# BasePCB.net
KiCad netlist of a schematic drawn in EAGLE
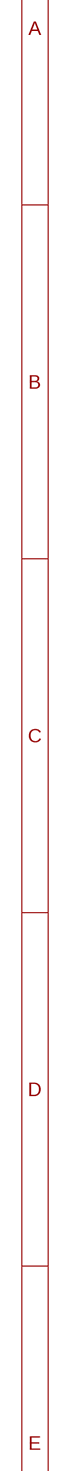
[diagram p0: schematic, sheet 1, part 1 of 2]
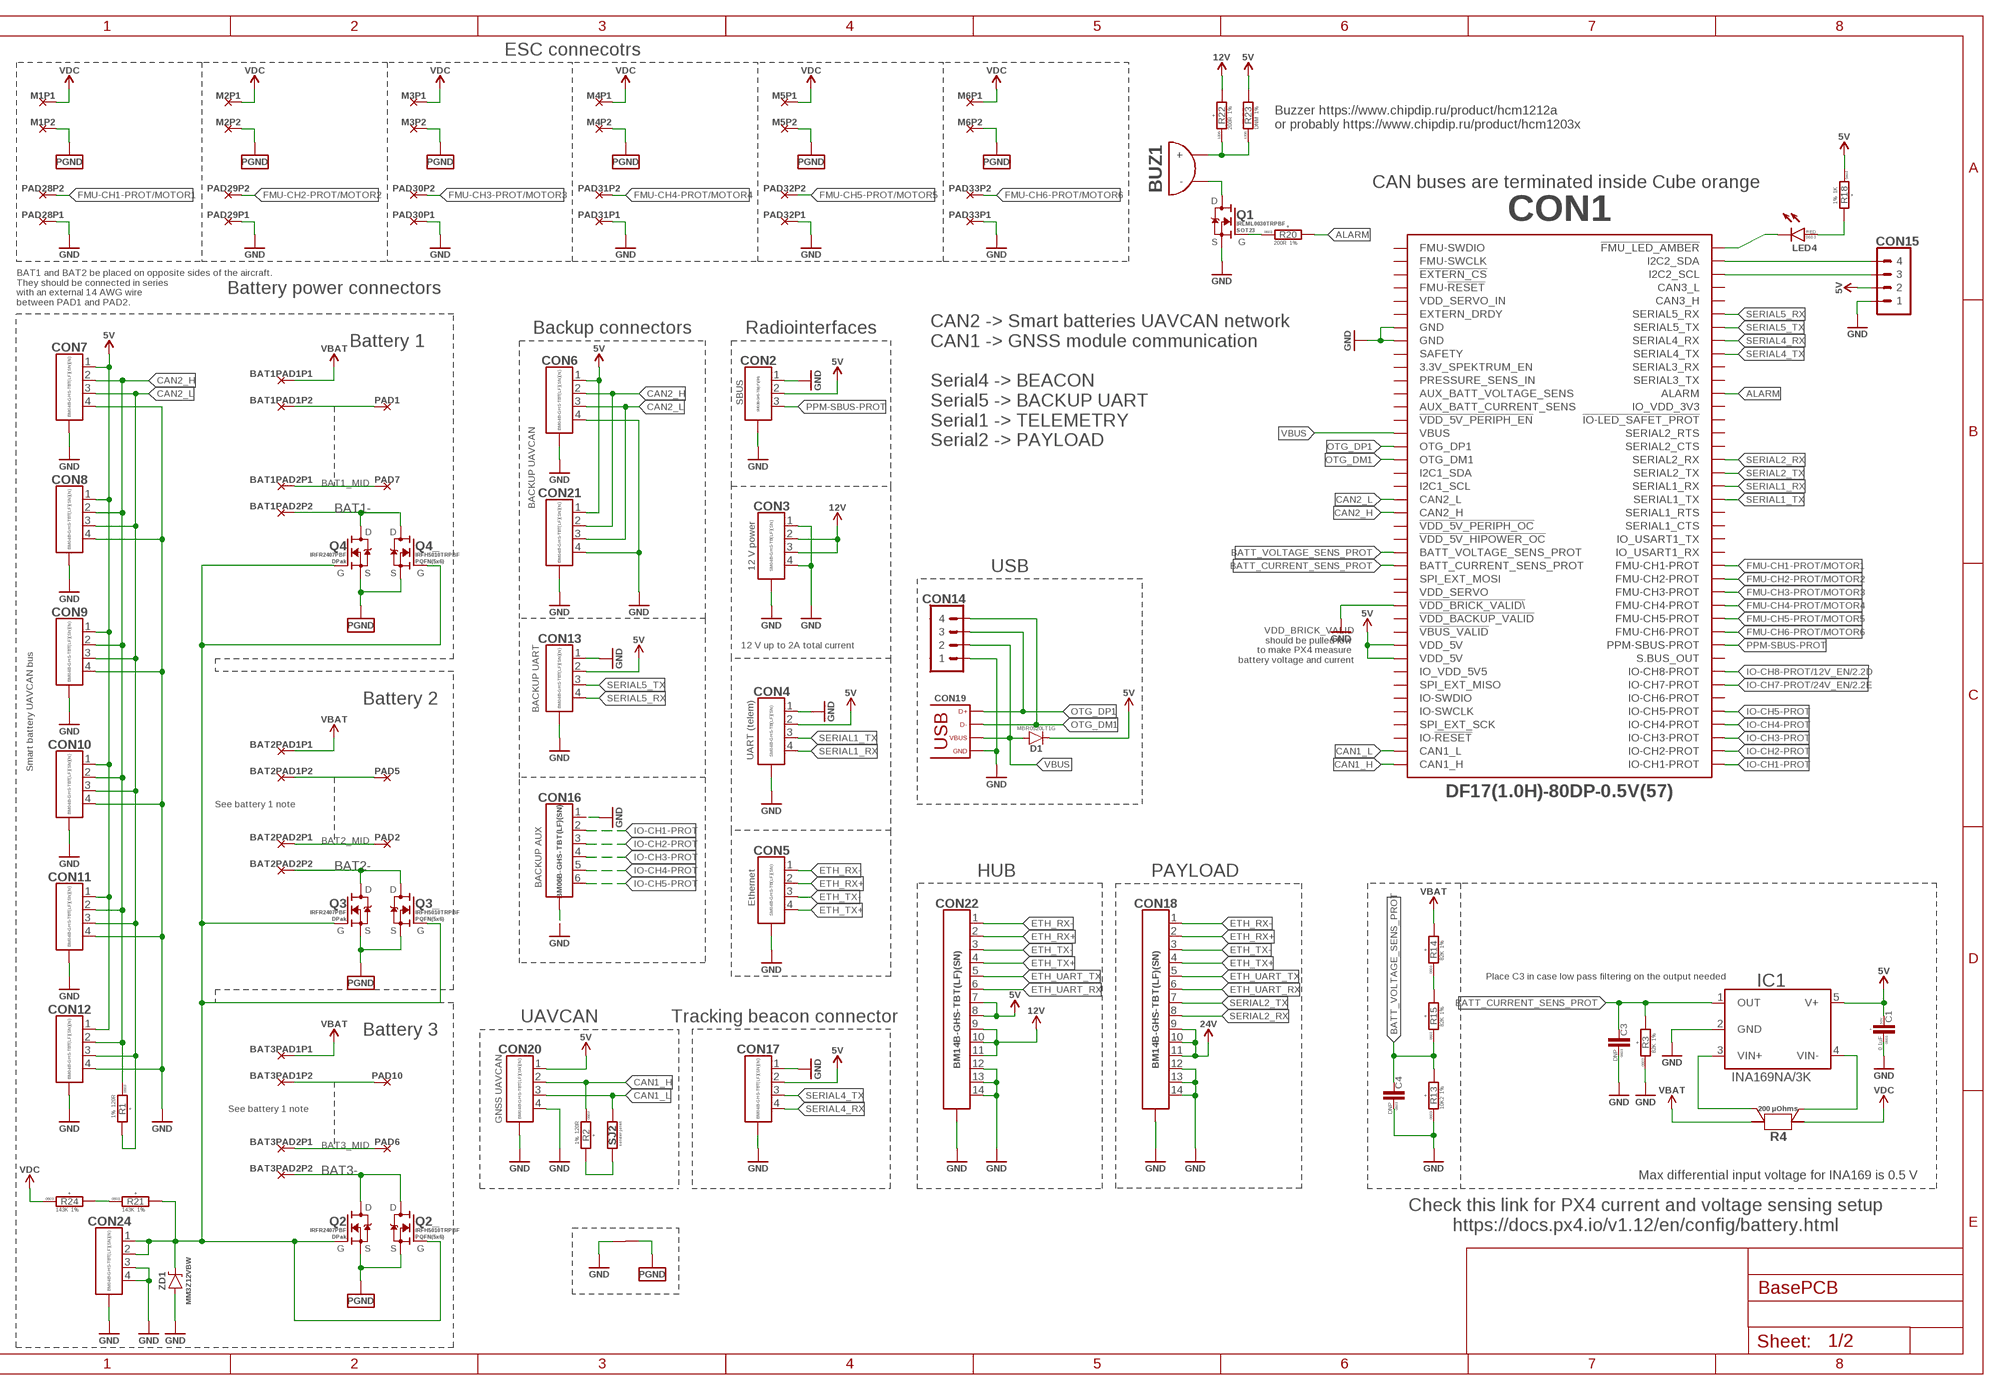
[diagram p1: schematic, sheet 1, part 2 of 2]
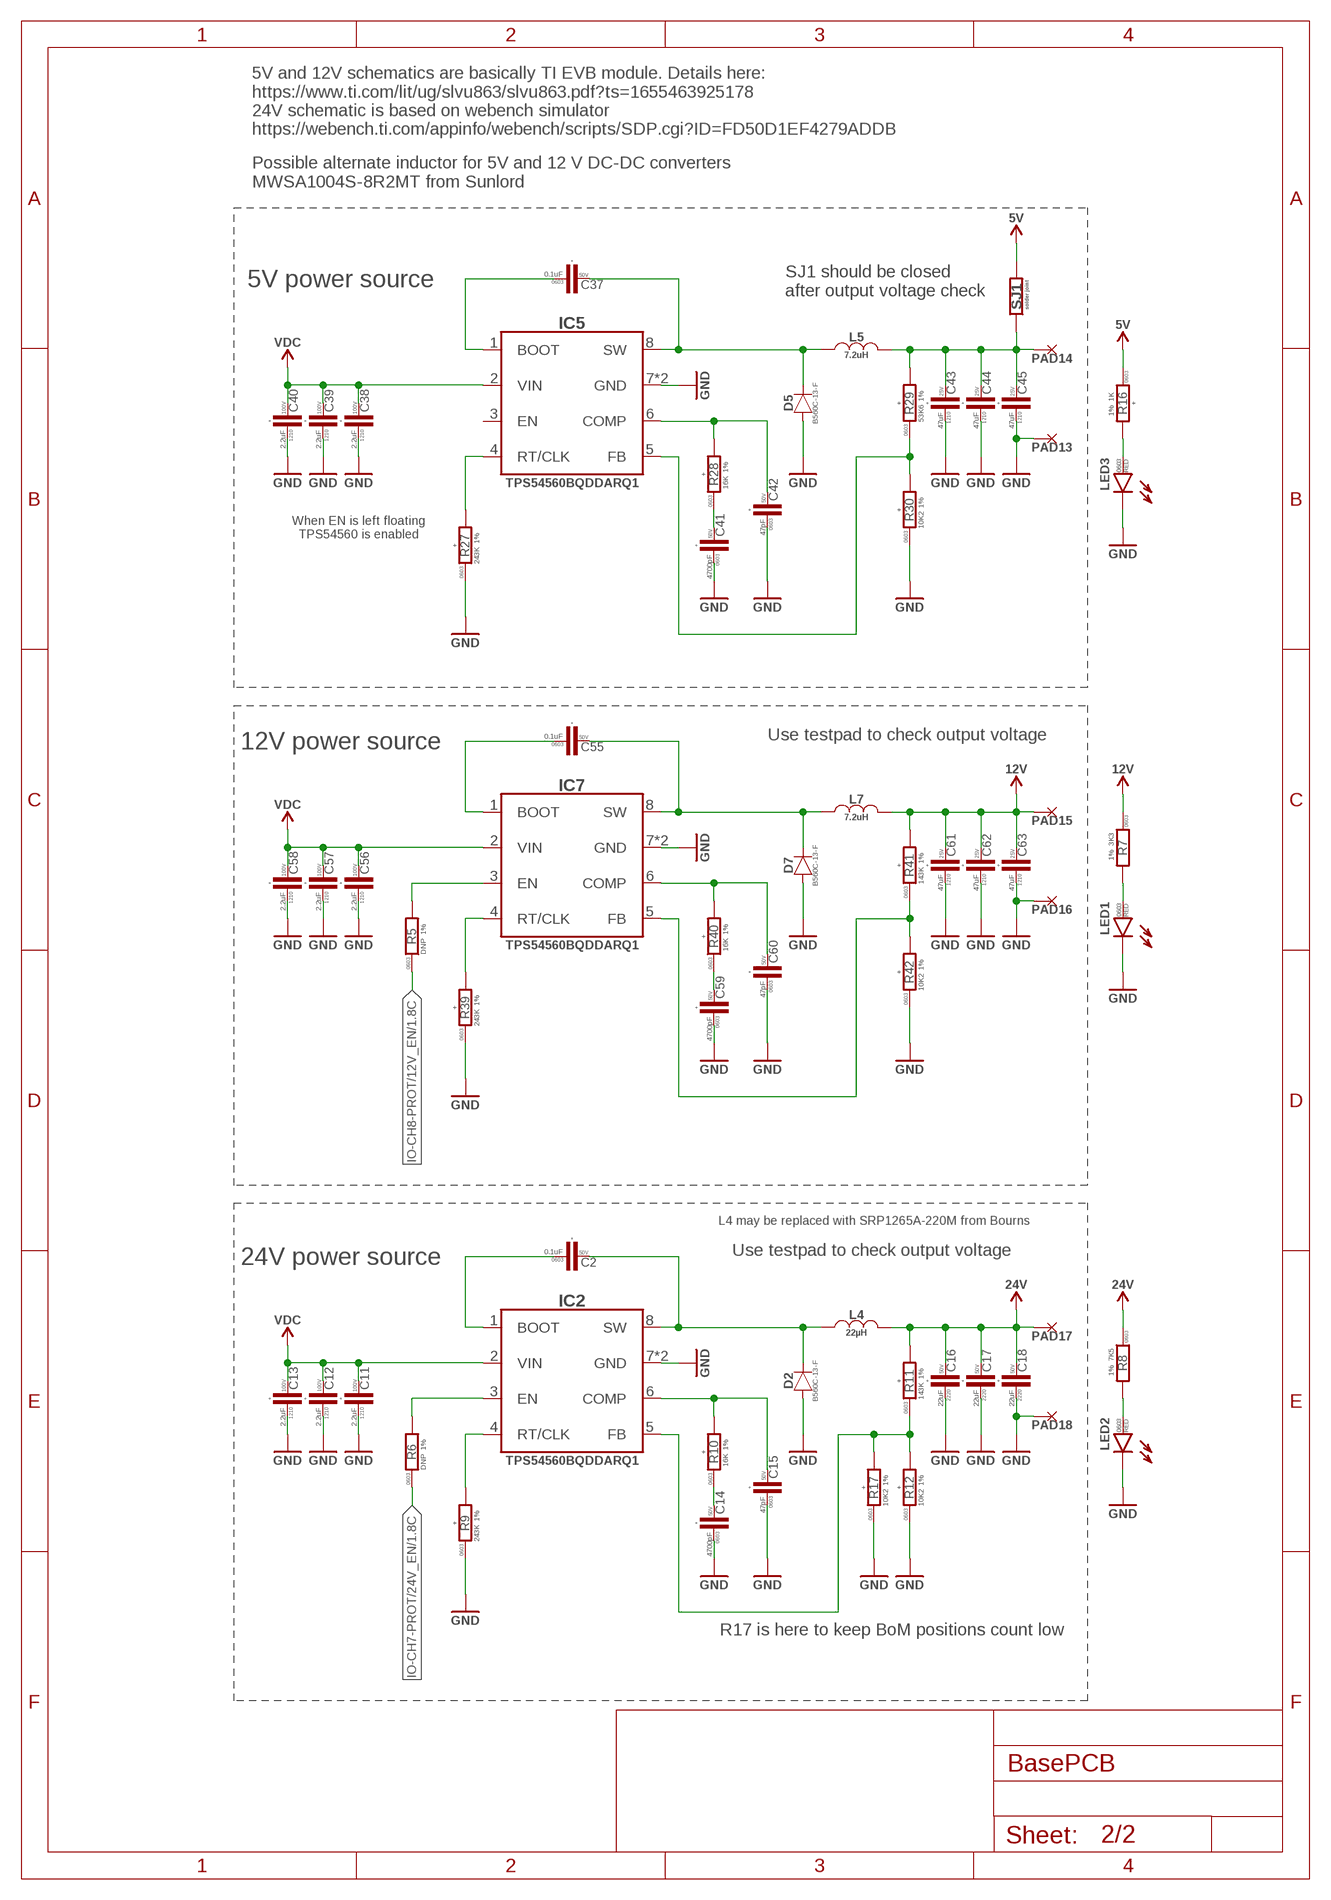
[diagram p2: schematic, sheet 2]

(export (version "E")
  (design (tool "Eeschema 10.0.6"))
  (components
    (comp (ref "C2")
      (value "0.1uF")
      (footprint "eagle-import:C0603")
      (fields
        (field (name "PACKAGE") "0603")
        (field (name "ALLOCATED") "+")
        (field (name "LCSC#") "C14663")
        (field (name "MANF") "YAGEO")
        (field (name "MANF#") "CC0603KRX7R9BB104")
        (field (name "VOLTAGE") "50V")
      )
      (libsource (lib "eagle-import") (part "C-0603"))
    )
    (comp (ref "C11")
      (value "2.2uF")
      (footprint "eagle-import:C1210")
      (fields
        (field (name "PACKAGE") "1210")
        (field (name "ALLOCATED") "+")
        (field (name "LCSC#") "C55151")
        (field (name "MANF") "Samsung Electro-Mechanics")
        (field (name "MANF#") "CL32B225KCJSNNE")
        (field (name "VOLTAGE") "100V")
      )
      (libsource (lib "eagle-import") (part "C-1210"))
    )
    (comp (ref "C12")
      (value "2.2uF")
      (footprint "eagle-import:C1210")
      (fields
        (field (name "PACKAGE") "1210")
        (field (name "ALLOCATED") "+")
        (field (name "LCSC#") "C55151")
        (field (name "MANF") "Samsung Electro-Mechanics")
        (field (name "MANF#") "CL32B225KCJSNNE")
        (field (name "VOLTAGE") "100V")
      )
      (libsource (lib "eagle-import") (part "C-1210"))
    )
    (comp (ref "C13")
      (value "2.2uF")
      (footprint "eagle-import:C1210")
      (fields
        (field (name "PACKAGE") "1210")
        (field (name "ALLOCATED") "+")
        (field (name "LCSC#") "C55151")
        (field (name "MANF") "Samsung Electro-Mechanics")
        (field (name "MANF#") "CL32B225KCJSNNE")
        (field (name "VOLTAGE") "100V")
      )
      (libsource (lib "eagle-import") (part "C-1210"))
    )
    (comp (ref "C14")
      (value "4700pF")
      (footprint "eagle-import:C0603")
      (fields
        (field (name "PACKAGE") "0603")
        (field (name "ALLOCATED") "+")
        (field (name "LCSC#") "C53987")
        (field (name "MANF") "FH(Guangdong Fenghua Advanced Tech)")
        (field (name "MANF#") "0603B472K500NT")
        (field (name "VOLTAGE") "50V")
      )
      (libsource (lib "eagle-import") (part "C-0603"))
    )
    (comp (ref "C15")
      (value "47pF")
      (footprint "eagle-import:C0603")
      (fields
        (field (name "PACKAGE") "0603")
        (field (name "ALLOCATED") "+")
        (field (name "LCSC#") "C1671")
        (field (name "MANF") "Samsung Electro-Mechanics")
        (field (name "MANF#") "CL10C470JB8NNNC")
        (field (name "VOLTAGE") "50V")
      )
      (libsource (lib "eagle-import") (part "C-0603"))
    )
    (comp (ref "C16")
      (value "22uF")
      (footprint "eagle-import:C2220")
      (fields
        (field (name "PACKAGE") "2220")
        (field (name "ALLOCATED") "+")
        (field (name "LCSC#") "C784103")
        (field (name "MANF") "PSA(Prosperity Dielectrics)")
        (field (name "MANF#") "FS55X226K500EHG")
        (field (name "VOLTAGE") "50V")
      )
      (libsource (lib "eagle-import") (part "C-C2220"))
    )
    (comp (ref "C17")
      (value "22uF")
      (footprint "eagle-import:C2220")
      (fields
        (field (name "PACKAGE") "2220")
        (field (name "ALLOCATED") "+")
        (field (name "LCSC#") "C784103")
        (field (name "MANF") "PSA(Prosperity Dielectrics)")
        (field (name "MANF#") "FS55X226K500EHG")
        (field (name "VOLTAGE") "50V")
      )
      (libsource (lib "eagle-import") (part "C-C2220"))
    )
    (comp (ref "C18")
      (value "22uF")
      (footprint "eagle-import:C2220")
      (fields
        (field (name "PACKAGE") "2220")
        (field (name "ALLOCATED") "+")
        (field (name "LCSC#") "C784103")
        (field (name "MANF") "PSA(Prosperity Dielectrics)")
        (field (name "MANF#") "FS55X226K500EHG")
        (field (name "VOLTAGE") "50V")
      )
      (libsource (lib "eagle-import") (part "C-C2220"))
    )
    (comp (ref "C37")
      (value "0.1uF")
      (footprint "eagle-import:C0603")
      (fields
        (field (name "PACKAGE") "0603")
        (field (name "ALLOCATED") "+")
        (field (name "LCSC#") "C14663")
        (field (name "MANF") "YAGEO")
        (field (name "MANF#") "CC0603KRX7R9BB104")
        (field (name "VOLTAGE") "50V")
      )
      (libsource (lib "eagle-import") (part "C-0603"))
    )
    (comp (ref "C38")
      (value "2.2uF")
      (footprint "eagle-import:C1210")
      (fields
        (field (name "PACKAGE") "1210")
        (field (name "ALLOCATED") "+")
        (field (name "LCSC#") "C55151")
        (field (name "MANF") "Samsung Electro-Mechanics")
        (field (name "MANF#") "CL32B225KCJSNNE")
        (field (name "VOLTAGE") "100V")
      )
      (libsource (lib "eagle-import") (part "C-1210"))
    )
    (comp (ref "C39")
      (value "2.2uF")
      (footprint "eagle-import:C1210")
      (fields
        (field (name "PACKAGE") "1210")
        (field (name "ALLOCATED") "+")
        (field (name "LCSC#") "C55151")
        (field (name "MANF") "Samsung Electro-Mechanics")
        (field (name "MANF#") "CL32B225KCJSNNE")
        (field (name "VOLTAGE") "100V")
      )
      (libsource (lib "eagle-import") (part "C-1210"))
    )
    (comp (ref "C40")
      (value "2.2uF")
      (footprint "eagle-import:C1210")
      (fields
        (field (name "PACKAGE") "1210")
        (field (name "ALLOCATED") "+")
        (field (name "LCSC#") "C55151")
        (field (name "MANF") "Samsung Electro-Mechanics")
        (field (name "MANF#") "CL32B225KCJSNNE")
        (field (name "VOLTAGE") "100V")
      )
      (libsource (lib "eagle-import") (part "C-1210"))
    )
    (comp (ref "C41")
      (value "4700pF")
      (footprint "eagle-import:C0603")
      (fields
        (field (name "PACKAGE") "0603")
        (field (name "ALLOCATED") "+")
        (field (name "LCSC#") "C53987")
        (field (name "MANF") "FH(Guangdong Fenghua Advanced Tech)")
        (field (name "MANF#") "0603B472K500NT")
        (field (name "VOLTAGE") "50V")
      )
      (libsource (lib "eagle-import") (part "C-0603"))
    )
    (comp (ref "C42")
      (value "47pF")
      (footprint "eagle-import:C0603")
      (fields
        (field (name "PACKAGE") "0603")
        (field (name "ALLOCATED") "+")
        (field (name "LCSC#") "C1671")
        (field (name "MANF") "Samsung Electro-Mechanics")
        (field (name "MANF#") "CL10C470JB8NNNC")
        (field (name "VOLTAGE") "50V")
      )
      (libsource (lib "eagle-import") (part "C-0603"))
    )
    (comp (ref "C43")
      (value "47uF")
      (footprint "eagle-import:C1210")
      (fields
        (field (name "PACKAGE") "1210")
        (field (name "ALLOCATED") "+")
        (field (name "LCSC#") "C90142")
        (field (name "MANF") "Taiyo Yuden")
        (field (name "MANF#") "TMK325ABJ476MM-P")
        (field (name "VOLTAGE") "25V")
      )
      (libsource (lib "eagle-import") (part "C-1210"))
    )
    (comp (ref "C44")
      (value "47uF")
      (footprint "eagle-import:C1210")
      (fields
        (field (name "PACKAGE") "1210")
        (field (name "ALLOCATED") "+")
        (field (name "LCSC#") "C90142")
        (field (name "MANF") "Taiyo Yuden")
        (field (name "MANF#") "TMK325ABJ476MM-P")
        (field (name "VOLTAGE") "25V")
      )
      (libsource (lib "eagle-import") (part "C-1210"))
    )
    (comp (ref "C45")
      (value "47uF")
      (footprint "eagle-import:C1210")
      (fields
        (field (name "PACKAGE") "1210")
        (field (name "ALLOCATED") "+")
        (field (name "LCSC#") "C90142")
        (field (name "MANF") "Taiyo Yuden")
        (field (name "MANF#") "TMK325ABJ476MM-P")
        (field (name "VOLTAGE") "25V")
      )
      (libsource (lib "eagle-import") (part "C-1210"))
    )
    (comp (ref "C55")
      (value "0.1uF")
      (footprint "eagle-import:C0603")
      (fields
        (field (name "PACKAGE") "0603")
        (field (name "ALLOCATED") "+")
        (field (name "LCSC#") "C14663")
        (field (name "MANF") "YAGEO")
        (field (name "MANF#") "CC0603KRX7R9BB104")
        (field (name "VOLTAGE") "50V")
      )
      (libsource (lib "eagle-import") (part "C-0603"))
    )
    (comp (ref "C56")
      (value "2.2uF")
      (footprint "eagle-import:C1210")
      (fields
        (field (name "PACKAGE") "1210")
        (field (name "ALLOCATED") "+")
        (field (name "LCSC#") "C55151")
        (field (name "MANF") "Samsung Electro-Mechanics")
        (field (name "MANF#") "CL32B225KCJSNNE")
        (field (name "VOLTAGE") "100V")
      )
      (libsource (lib "eagle-import") (part "C-1210"))
    )
    (comp (ref "C57")
      (value "2.2uF")
      (footprint "eagle-import:C1210")
      (fields
        (field (name "PACKAGE") "1210")
        (field (name "ALLOCATED") "+")
        (field (name "LCSC#") "C55151")
        (field (name "MANF") "Samsung Electro-Mechanics")
        (field (name "MANF#") "CL32B225KCJSNNE")
        (field (name "VOLTAGE") "100V")
      )
      (libsource (lib "eagle-import") (part "C-1210"))
    )
    (comp (ref "C58")
      (value "2.2uF")
      (footprint "eagle-import:C1210")
      (fields
        (field (name "PACKAGE") "1210")
        (field (name "ALLOCATED") "+")
        (field (name "LCSC#") "C55151")
        (field (name "MANF") "Samsung Electro-Mechanics")
        (field (name "MANF#") "CL32B225KCJSNNE")
        (field (name "VOLTAGE") "100V")
      )
      (libsource (lib "eagle-import") (part "C-1210"))
    )
    (comp (ref "C59")
      (value "4700pF")
      (footprint "eagle-import:C0603")
      (fields
        (field (name "PACKAGE") "0603")
        (field (name "ALLOCATED") "+")
        (field (name "LCSC#") "C53987")
        (field (name "MANF") "FH(Guangdong Fenghua Advanced Tech)")
        (field (name "MANF#") "0603B472K500NT")
        (field (name "VOLTAGE") "50V")
      )
      (libsource (lib "eagle-import") (part "C-0603"))
    )
    (comp (ref "C60")
      (value "47pF")
      (footprint "eagle-import:C0603")
      (fields
        (field (name "PACKAGE") "0603")
        (field (name "ALLOCATED") "+")
        (field (name "LCSC#") "C1671")
        (field (name "MANF") "Samsung Electro-Mechanics")
        (field (name "MANF#") "CL10C470JB8NNNC")
        (field (name "VOLTAGE") "50V")
      )
      (libsource (lib "eagle-import") (part "C-0603"))
    )
    (comp (ref "C61")
      (value "47uF")
      (footprint "eagle-import:C1210")
      (fields
        (field (name "PACKAGE") "1210")
        (field (name "ALLOCATED") "+")
        (field (name "LCSC#") "C90142")
        (field (name "MANF") "Taiyo Yuden")
        (field (name "MANF#") "TMK325ABJ476MM-P")
        (field (name "VOLTAGE") "25V")
      )
      (libsource (lib "eagle-import") (part "C-1210"))
    )
    (comp (ref "C62")
      (value "47uF")
      (footprint "eagle-import:C1210")
      (fields
        (field (name "PACKAGE") "1210")
        (field (name "ALLOCATED") "+")
        (field (name "LCSC#") "C90142")
        (field (name "MANF") "Taiyo Yuden")
        (field (name "MANF#") "TMK325ABJ476MM-P")
        (field (name "VOLTAGE") "25V")
      )
      (libsource (lib "eagle-import") (part "C-1210"))
    )
    (comp (ref "C63")
      (value "47uF")
      (footprint "eagle-import:C1210")
      (fields
        (field (name "PACKAGE") "1210")
        (field (name "ALLOCATED") "+")
        (field (name "LCSC#") "C90142")
        (field (name "MANF") "Taiyo Yuden")
        (field (name "MANF#") "TMK325ABJ476MM-P")
        (field (name "VOLTAGE") "25V")
      )
      (libsource (lib "eagle-import") (part "C-1210"))
    )
    (comp (ref "D2")
      (value "B560C")
      (footprint "eagle-import:DO-214AB(SMC)")
      (fields (field (name "MANF#") "B560C-13-F") (field (name "MANF") "Diodes Incorporated"))
      (libsource (lib "eagle-import") (part "B560C"))
    )
    (comp (ref "D5")
      (value "B560C")
      (footprint "eagle-import:DO-214AB(SMC)")
      (fields (field (name "MANF#") "B560C-13-F") (field (name "MANF") "Diodes Incorporated"))
      (libsource (lib "eagle-import") (part "B560C"))
    )
    (comp (ref "D7")
      (value "B560C")
      (footprint "eagle-import:DO-214AB(SMC)")
      (fields (field (name "MANF#") "B560C-13-F") (field (name "MANF") "Diodes Incorporated"))
      (libsource (lib "eagle-import") (part "B560C"))
    )
    (comp (ref "IC2")
      (value "TPS54560B")
      (footprint "eagle-import:SOIC8-POWERPAD")
      (fields (field (name "MANF#") "TPS54560BQDDARQ1") (field (name "MANF") "Texas Instruments"))
      (libsource (lib "eagle-import") (part "TPS54560B"))
    )
    (comp (ref "IC5")
      (value "TPS54560B")
      (footprint "eagle-import:SOIC8-POWERPAD")
      (fields (field (name "MANF#") "TPS54560BQDDARQ1") (field (name "MANF") "Texas Instruments"))
      (libsource (lib "eagle-import") (part "TPS54560B"))
    )
    (comp (ref "IC7")
      (value "TPS54560B")
      (footprint "eagle-import:SOIC8-POWERPAD")
      (fields (field (name "MANF#") "TPS54560BQDDARQ1") (field (name "MANF") "Texas Instruments"))
      (libsource (lib "eagle-import") (part "TPS54560B"))
    )
    (comp (ref "L4")
      (value "22µH")
      (footprint "eagle-import:MWSA1206S")
      (fields (field (name "MANF") "SUNLORD"))
      (libsource (lib "eagle-import") (part "22µH-MWSA1206S"))
    )
    (comp (ref "L5")
      (value "7.2uH")
      (footprint "eagle-import:1064")
      (fields (field (name "MANF") "Wurth Elektronik"))
      (libsource (lib "eagle-import") (part "7.2µH-1064"))
    )
    (comp (ref "L7")
      (value "7.2uH")
      (footprint "eagle-import:1064")
      (fields (field (name "MANF") "Wurth Elektronik"))
      (libsource (lib "eagle-import") (part "7.2µH-1064"))
    )
    (comp (ref "LED1")
      (value "LED-0603")
      (footprint "eagle-import:LED0603")
      (fields
        (field (name "PACKAGE") "0603")
        (field (name "COLOR") "RED")
        (field (name "LCSC#") "C2286")
        (field (name "MANF") "Hubei KENTO Elec")
        (field (name "MANF#") "KT-0603R")
      )
      (libsource (lib "eagle-import") (part "LED-0603"))
    )
    (comp (ref "LED2")
      (value "LED-0603")
      (footprint "eagle-import:LED0603")
      (fields
        (field (name "PACKAGE") "0603")
        (field (name "COLOR") "RED")
        (field (name "LCSC#") "C2286")
        (field (name "MANF") "Hubei KENTO Elec")
        (field (name "MANF#") "KT-0603R")
      )
      (libsource (lib "eagle-import") (part "LED-0603"))
    )
    (comp (ref "LED3")
      (value "LED-0603")
      (footprint "eagle-import:LED0603")
      (fields
        (field (name "PACKAGE") "0603")
        (field (name "COLOR") "RED")
        (field (name "LCSC#") "C2286")
        (field (name "MANF") "Hubei KENTO Elec")
        (field (name "MANF#") "KT-0603R")
      )
      (libsource (lib "eagle-import") (part "LED-0603"))
    )
    (comp (ref "PAD13")
      (value "PAD-S_2X2")
      (footprint "eagle-import:2х2")
      (libsource (lib "eagle-import") (part "PAD-S_2X2"))
    )
    (comp (ref "PAD14")
      (value "PAD-S_2X2")
      (footprint "eagle-import:2х2")
      (libsource (lib "eagle-import") (part "PAD-S_2X2"))
    )
    (comp (ref "PAD15")
      (value "PAD-S_2X2")
      (footprint "eagle-import:2х2")
      (libsource (lib "eagle-import") (part "PAD-S_2X2"))
    )
    (comp (ref "PAD16")
      (value "PAD-S_2X2")
      (footprint "eagle-import:2х2")
      (libsource (lib "eagle-import") (part "PAD-S_2X2"))
    )
    (comp (ref "PAD17")
      (value "PAD-S_2X2")
      (footprint "eagle-import:2х2")
      (libsource (lib "eagle-import") (part "PAD-S_2X2"))
    )
    (comp (ref "PAD18")
      (value "PAD-S_2X2")
      (footprint "eagle-import:2х2")
      (libsource (lib "eagle-import") (part "PAD-S_2X2"))
    )
    (comp (ref "R5")
      (value "DNP")
      (footprint "eagle-import:R0603")
      (fields (field (name "PACKAGE") "0603") (field (name "TOLERANCE") "1%"))
      (libsource (lib "eagle-import") (part "R-0603-1%"))
    )
    (comp (ref "R6")
      (value "DNP")
      (footprint "eagle-import:R0603")
      (fields (field (name "PACKAGE") "0603") (field (name "TOLERANCE") "1%"))
      (libsource (lib "eagle-import") (part "R-0603-1%"))
    )
    (comp (ref "R7")
      (value "3K3")
      (footprint "eagle-import:R0603")
      (fields
        (field (name "PACKAGE") "0603")
        (field (name "TOLERANCE") "1%")
        (field (name "LCSC#") "C22978")
        (field (name "MANF") "UNI-ROYAL(Uniroyal Elec)")
        (field (name "MANF#") "0603WAF3301T5E")
      )
      (libsource (lib "eagle-import") (part "R-0603-1%"))
    )
    (comp (ref "R8")
      (value "7K5")
      (footprint "eagle-import:R0603")
      (fields
        (field (name "PACKAGE") "0603")
        (field (name "TOLERANCE") "1%")
        (field (name "LCSC#") "C23234")
        (field (name "MANF") "UNI-ROYAL(Uniroyal Elec)")
        (field (name "MANF#") "0603WAF7501T5E")
      )
      (libsource (lib "eagle-import") (part "R-0603-1%"))
    )
    (comp (ref "R9")
      (value "243K")
      (footprint "eagle-import:R0603")
      (fields
        (field (name "PACKAGE") "0603")
        (field (name "TOLERANCE") "1%")
        (field (name "ALLOCATED") "+")
        (field (name "LCSC#") "C23351")
        (field (name "MANF") "UNI-ROYAL(Uniroyal Elec)")
        (field (name "MANF#") "0603WAF2433T5E")
      )
      (libsource (lib "eagle-import") (part "R-0603-1%"))
    )
    (comp (ref "R10")
      (value "16K")
      (footprint "eagle-import:R0603")
      (fields
        (field (name "PACKAGE") "0603")
        (field (name "TOLERANCE") "1%")
        (field (name "ALLOCATED") "+")
        (field (name "LCSC#") "C4210")
        (field (name "MANF") "UNI-ROYAL(Uniroyal Elec)")
        (field (name "MANF#") "0603WAF1602T5E")
      )
      (libsource (lib "eagle-import") (part "R-0603-1%"))
    )
    (comp (ref "R11")
      (value "143K")
      (footprint "eagle-import:R0603")
      (fields
        (field (name "PACKAGE") "0603")
        (field (name "TOLERANCE") "1%")
        (field (name "ALLOCATED") "+")
        (field (name "LCSC#") "C22877")
        (field (name "MANF") "UNI-ROYAL(Uniroyal Elec)")
        (field (name "MANF#") "0603WAF1433T5E")
      )
      (libsource (lib "eagle-import") (part "R-0603-1%"))
    )
    (comp (ref "R12")
      (value "10K2")
      (footprint "eagle-import:R0603")
      (fields
        (field (name "PACKAGE") "0603")
        (field (name "TOLERANCE") "1%")
        (field (name "ALLOCATED") "+")
        (field (name "LCSC#") "C22772")
        (field (name "MANF") "UNI-ROYAL(Uniroyal Elec)")
        (field (name "MANF#") "0603WAF1022T5E")
      )
      (libsource (lib "eagle-import") (part "R-0603-1%"))
    )
    (comp (ref "R16")
      (value "1K")
      (footprint "eagle-import:R0603")
      (fields
        (field (name "PACKAGE") "0603")
        (field (name "TOLERANCE") "1%")
        (field (name "ALLOCATED") "+")
        (field (name "LCSC#") "C21190")
        (field (name "MANF") "UNI-ROYAL(Uniroyal Elec)")
        (field (name "MANF#") "0603WAF1001T5E")
      )
      (libsource (lib "eagle-import") (part "R-0603-1%"))
    )
    (comp (ref "R17")
      (value "10K2")
      (footprint "eagle-import:R0603")
      (fields
        (field (name "PACKAGE") "0603")
        (field (name "TOLERANCE") "1%")
        (field (name "ALLOCATED") "+")
        (field (name "LCSC#") "C22772")
        (field (name "MANF") "UNI-ROYAL(Uniroyal Elec)")
        (field (name "MANF#") "0603WAF1022T5E")
      )
      (libsource (lib "eagle-import") (part "R-0603-1%"))
    )
    (comp (ref "R27")
      (value "243K")
      (footprint "eagle-import:R0603")
      (fields
        (field (name "PACKAGE") "0603")
        (field (name "TOLERANCE") "1%")
        (field (name "ALLOCATED") "+")
        (field (name "LCSC#") "C23351")
        (field (name "MANF") "UNI-ROYAL(Uniroyal Elec)")
        (field (name "MANF#") "0603WAF2433T5E")
      )
      (libsource (lib "eagle-import") (part "R-0603-1%"))
    )
    (comp (ref "R28")
      (value "16K")
      (footprint "eagle-import:R0603")
      (fields
        (field (name "PACKAGE") "0603")
        (field (name "TOLERANCE") "1%")
        (field (name "ALLOCATED") "+")
        (field (name "LCSC#") "C4210")
        (field (name "MANF") "UNI-ROYAL(Uniroyal Elec)")
        (field (name "MANF#") "0603WAF1602T5E")
      )
      (libsource (lib "eagle-import") (part "R-0603-1%"))
    )
    (comp (ref "R29")
      (value "53K6")
      (footprint "eagle-import:R0603")
      (fields
        (field (name "PACKAGE") "0603")
        (field (name "TOLERANCE") "1%")
        (field (name "ALLOCATED") "+")
        (field (name "LCSC#") "C23074")
        (field (name "MANF") "UNI-ROYAL(Uniroyal Elec)")
        (field (name "MANF#") "0603WAF5362T5E")
      )
      (libsource (lib "eagle-import") (part "R-0603-1%"))
    )
    (comp (ref "R30")
      (value "10K2")
      (footprint "eagle-import:R0603")
      (fields
        (field (name "PACKAGE") "0603")
        (field (name "TOLERANCE") "1%")
        (field (name "ALLOCATED") "+")
        (field (name "LCSC#") "C22772")
        (field (name "MANF") "UNI-ROYAL(Uniroyal Elec)")
        (field (name "MANF#") "0603WAF1022T5E")
      )
      (libsource (lib "eagle-import") (part "R-0603-1%"))
    )
    (comp (ref "R39")
      (value "243K")
      (footprint "eagle-import:R0603")
      (fields
        (field (name "PACKAGE") "0603")
        (field (name "TOLERANCE") "1%")
        (field (name "ALLOCATED") "+")
        (field (name "LCSC#") "C23351")
        (field (name "MANF") "UNI-ROYAL(Uniroyal Elec)")
        (field (name "MANF#") "0603WAF2433T5E")
      )
      (libsource (lib "eagle-import") (part "R-0603-1%"))
    )
    (comp (ref "R40")
      (value "16K")
      (footprint "eagle-import:R0603")
      (fields
        (field (name "PACKAGE") "0603")
        (field (name "TOLERANCE") "1%")
        (field (name "ALLOCATED") "+")
        (field (name "LCSC#") "C4210")
        (field (name "MANF") "UNI-ROYAL(Uniroyal Elec)")
        (field (name "MANF#") "0603WAF1602T5E")
      )
      (libsource (lib "eagle-import") (part "R-0603-1%"))
    )
    (comp (ref "R41")
      (value "143K")
      (footprint "eagle-import:R0603")
      (fields
        (field (name "PACKAGE") "0603")
        (field (name "TOLERANCE") "1%")
        (field (name "ALLOCATED") "+")
        (field (name "LCSC#") "C22877")
        (field (name "MANF") "UNI-ROYAL(Uniroyal Elec)")
        (field (name "MANF#") "0603WAF1433T5E")
      )
      (libsource (lib "eagle-import") (part "R-0603-1%"))
    )
    (comp (ref "R42")
      (value "10K2")
      (footprint "eagle-import:R0603")
      (fields
        (field (name "PACKAGE") "0603")
        (field (name "TOLERANCE") "1%")
        (field (name "ALLOCATED") "+")
        (field (name "LCSC#") "C22772")
        (field (name "MANF") "UNI-ROYAL(Uniroyal Elec)")
        (field (name "MANF#") "0603WAF1022T5E")
      )
      (libsource (lib "eagle-import") (part "R-0603-1%"))
    )
    (comp (ref "SJ1")
      (value "SOLDER_JOINT-SJ1")
      (footprint "eagle-import:RES_0")
      (libsource (lib "eagle-import") (part "SOLDER_JOINT-SJ1"))
    )
    (comp (ref "BAT1PAD1")
      (value "PAD_PAIR-4X10")
      (footprint "eagle-import:4X10_PAIR")
      (libsource (lib "eagle-import") (part "PAD_PAIR-4X10"))
    )
    (comp (ref "BAT1PAD2")
      (value "PAD_PAIR-4X10")
      (footprint "eagle-import:4X10_PAIR")
      (libsource (lib "eagle-import") (part "PAD_PAIR-4X10"))
    )
    (comp (ref "BAT2PAD1")
      (value "PAD_PAIR-4X10")
      (footprint "eagle-import:4X10_PAIR")
      (libsource (lib "eagle-import") (part "PAD_PAIR-4X10"))
    )
    (comp (ref "BAT2PAD2")
      (value "PAD_PAIR-4X10")
      (footprint "eagle-import:4X10_PAIR")
      (libsource (lib "eagle-import") (part "PAD_PAIR-4X10"))
    )
    (comp (ref "BAT3PAD1")
      (value "PAD_PAIR-4X10")
      (footprint "eagle-import:4X10_PAIR")
      (libsource (lib "eagle-import") (part "PAD_PAIR-4X10"))
    )
    (comp (ref "BAT3PAD2")
      (value "PAD_PAIR-4X10")
      (footprint "eagle-import:4X10_PAIR")
      (libsource (lib "eagle-import") (part "PAD_PAIR-4X10"))
    )
    (comp (ref "BUZ1")
      (value "BUZZER-ЕР-12MM")
      (footprint "eagle-import:BUZZER_12MM")
      (fields (field (name "MANF") "JL World") (field (name "MANF#") "HCM1212A"))
      (libsource (lib "eagle-import") (part "BUZZER-ЕР-12MM"))
    )
    (comp (ref "C1")
      (value "0.1uF")
      (footprint "eagle-import:C0603")
      (fields
        (field (name "PACKAGE") "0603")
        (field (name "ALLOCATED") "+")
        (field (name "LCSC#") "C14663")
        (field (name "MANF") "YAGEO")
        (field (name "MANF#") "CC0603KRX7R9BB104")
        (field (name "VOLTAGE") "50V")
      )
      (libsource (lib "eagle-import") (part "C-0603"))
    )
    (comp (ref "C3")
      (value "DNP")
      (footprint "eagle-import:C0603")
      (fields (field (name "PACKAGE") "0603"))
      (libsource (lib "eagle-import") (part "C-0603"))
    )
    (comp (ref "C4")
      (value "DNP")
      (footprint "eagle-import:C0603")
      (fields (field (name "PACKAGE") "0603"))
      (libsource (lib "eagle-import") (part "C-0603"))
    )
    (comp (ref "CON1")
      (value "CUBE_ORANGE_")
      (footprint "eagle-import:CUBE_ORANGE")
      (fields (field (name "MANF#") "DF17(1.0H)-80DP-0.5V(57)") (field (name "MANF") "HIROSE"))
      (libsource (lib "eagle-import") (part "CUBE_ORANGE_"))
    )
    (comp (ref "CON2")
      (value "CON-3P-TABS-JST-GH-SIDE")
      (footprint "eagle-import:SM03B-GHS-TB")
      (fields (field (name "MANF#") "SM03B-GHS-TB(LF)(SN) ") (field (name "MANF") "JST Sales America Inc"))
      (libsource (lib "eagle-import") (part "CON-3P-TABS-JST-GH-SIDE"))
    )
    (comp (ref "CON3")
      (value "CON-4P-TABS-JST-GH-SIDE")
      (footprint "eagle-import:SM04B-GHS-TB")
      (fields (field (name "MANF#") "SM04B-GHS-TB(LF)(SN)") (field (name "MANF") "JST Sales America Inc"))
      (libsource (lib "eagle-import") (part "CON-4P-TABS-JST-GH-SIDE"))
    )
    (comp (ref "CON4")
      (value "CON-4P-TABS-JST-GH-SIDE")
      (footprint "eagle-import:SM04B-GHS-TB")
      (fields (field (name "MANF#") "SM04B-GHS-TB(LF)(SN)") (field (name "MANF") "JST Sales America Inc"))
      (libsource (lib "eagle-import") (part "CON-4P-TABS-JST-GH-SIDE"))
    )
    (comp (ref "CON5")
      (value "CON-4P-TABS-JST-GH-SIDE")
      (footprint "eagle-import:SM04B-GHS-TB")
      (fields (field (name "MANF#") "SM04B-GHS-TB(LF)(SN)") (field (name "MANF") "JST Sales America Inc"))
      (libsource (lib "eagle-import") (part "CON-4P-TABS-JST-GH-SIDE"))
    )
    (comp (ref "CON6")
      (value "CON-4P-TABS-JST-GH-TOP")
      (footprint "eagle-import:BM04B-GHS-TB")
      (fields (field (name "MANF#") "BM04B-GHS-TBT(LF)(SN)(N)") (field (name "MANF") "JST Sales America Inc"))
      (libsource (lib "eagle-import") (part "CON-4P-TABS-JST-GH-TOP"))
    )
    (comp (ref "CON7")
      (value "CON-4P-TABS-JST-GH-TOP")
      (footprint "eagle-import:BM04B-GHS-TB")
      (fields (field (name "MANF#") "BM04B-GHS-TBT(LF)(SN)(N)") (field (name "MANF") "JST Sales America Inc"))
      (libsource (lib "eagle-import") (part "CON-4P-TABS-JST-GH-TOP"))
    )
    (comp (ref "CON8")
      (value "CON-4P-TABS-JST-GH-TOP")
      (footprint "eagle-import:BM04B-GHS-TB")
      (fields (field (name "MANF#") "BM04B-GHS-TBT(LF)(SN)(N)") (field (name "MANF") "JST Sales America Inc"))
      (libsource (lib "eagle-import") (part "CON-4P-TABS-JST-GH-TOP"))
    )
    (comp (ref "CON9")
      (value "CON-4P-TABS-JST-GH-TOP")
      (footprint "eagle-import:BM04B-GHS-TB")
      (fields (field (name "MANF#") "BM04B-GHS-TBT(LF)(SN)(N)") (field (name "MANF") "JST Sales America Inc"))
      (libsource (lib "eagle-import") (part "CON-4P-TABS-JST-GH-TOP"))
    )
    (comp (ref "CON10")
      (value "CON-4P-TABS-JST-GH-TOP")
      (footprint "eagle-import:BM04B-GHS-TB")
      (fields (field (name "MANF#") "BM04B-GHS-TBT(LF)(SN)(N)") (field (name "MANF") "JST Sales America Inc"))
      (libsource (lib "eagle-import") (part "CON-4P-TABS-JST-GH-TOP"))
    )
    (comp (ref "CON11")
      (value "CON-4P-TABS-JST-GH-TOP")
      (footprint "eagle-import:BM04B-GHS-TB")
      (fields (field (name "MANF#") "BM04B-GHS-TBT(LF)(SN)(N)") (field (name "MANF") "JST Sales America Inc"))
      (libsource (lib "eagle-import") (part "CON-4P-TABS-JST-GH-TOP"))
    )
    (comp (ref "CON12")
      (value "CON-4P-TABS-JST-GH-TOP")
      (footprint "eagle-import:BM04B-GHS-TB")
      (fields (field (name "MANF#") "BM04B-GHS-TBT(LF)(SN)(N)") (field (name "MANF") "JST Sales America Inc"))
      (libsource (lib "eagle-import") (part "CON-4P-TABS-JST-GH-TOP"))
    )
    (comp (ref "CON13")
      (value "CON-4P-TABS-JST-GH-TOP")
      (footprint "eagle-import:BM04B-GHS-TB")
      (fields (field (name "MANF#") "BM04B-GHS-TBT(LF)(SN)(N)") (field (name "MANF") "JST Sales America Inc"))
      (libsource (lib "eagle-import") (part "CON-4P-TABS-JST-GH-TOP"))
    )
    (comp (ref "CON14")
      (value "PINHEAD_1X04-2.54")
      (footprint "eagle-import:1X04-PTH-2.54")
      (libsource (lib "eagle-import") (part "PINHEAD_1X04-2.54"))
    )
    (comp (ref "CON15")
      (value "PINHEAD_1X04-2.54")
      (footprint "eagle-import:1X04-PTH-2.54")
      (libsource (lib "eagle-import") (part "PINHEAD_1X04-2.54"))
    )
    (comp (ref "CON16")
      (value "CON-6P-TABS-JST-GH-TOP")
      (footprint "eagle-import:BM06B-GHS-TBT")
      (fields (field (name "MANF#") "BM06B-GHS-TBT(LF)(SN) ") (field (name "MANF") "JST Sales America Inc"))
      (libsource (lib "eagle-import") (part "CON-6P-TABS-JST-GH-TOP"))
    )
    (comp (ref "CON17")
      (value "CON-4P-TABS-JST-GH-TOP")
      (footprint "eagle-import:BM04B-GHS-TB")
      (fields (field (name "MANF#") "BM04B-GHS-TBT(LF)(SN)(N)") (field (name "MANF") "JST Sales America Inc"))
      (libsource (lib "eagle-import") (part "CON-4P-TABS-JST-GH-TOP"))
    )
    (comp (ref "CON18")
      (value "CON-14P-TABS-JST-GH-TOP")
      (footprint "eagle-import:BM14B-GHS-TBT")
      (fields (field (name "MANF#") "BM14B-GHS-TBT(LF)(SN)") (field (name "MANF") "JST Sales America"))
      (libsource (lib "eagle-import") (part "CON-14P-TABS-JST-GH-TOP"))
    )
    (comp (ref "CON19")
      (value "USB-TYPE-C-VERT-PROD")
      (footprint "eagle-import:2047110001-PROD")
      (fields (field (name "MANF") "Molex"))
      (libsource (lib "eagle-import") (part "USB-TYPE-C-VERT-PROD"))
    )
    (comp (ref "CON20")
      (value "CON-4P-TABS-JST-GH-TOP")
      (footprint "eagle-import:BM04B-GHS-TB")
      (fields (field (name "MANF#") "BM04B-GHS-TBT(LF)(SN)(N)") (field (name "MANF") "JST Sales America Inc"))
      (libsource (lib "eagle-import") (part "CON-4P-TABS-JST-GH-TOP"))
    )
    (comp (ref "CON21")
      (value "CON-4P-TABS-JST-GH-TOP")
      (footprint "eagle-import:BM04B-GHS-TB")
      (fields (field (name "MANF#") "BM04B-GHS-TBT(LF)(SN)(N)") (field (name "MANF") "JST Sales America Inc"))
      (libsource (lib "eagle-import") (part "CON-4P-TABS-JST-GH-TOP"))
    )
    (comp (ref "CON22")
      (value "CON-14P-TABS-JST-GH-TOP")
      (footprint "eagle-import:BM14B-GHS-TBT")
      (fields (field (name "MANF#") "BM14B-GHS-TBT(LF)(SN)") (field (name "MANF") "JST Sales America"))
      (libsource (lib "eagle-import") (part "CON-14P-TABS-JST-GH-TOP"))
    )
    (comp (ref "CON24")
      (value "CON-4P-TABS-JST-GH-TOP")
      (footprint "eagle-import:BM04B-GHS-TB")
      (fields (field (name "MANF#") "BM04B-GHS-TBT(LF)(SN)(N)") (field (name "MANF") "JST Sales America Inc"))
      (libsource (lib "eagle-import") (part "CON-4P-TABS-JST-GH-TOP"))
    )
    (comp (ref "D1")
      (value "MBR0520L-SOD123")
      (footprint "eagle-import:SOD123")
      (fields (field (name "MANF#") "MBR0520LT1G") (field (name "MANF") "ON Semiconductor"))
      (libsource (lib "eagle-import") (part "MBR0520L-SOD123"))
    )
    (comp (ref "IC1")
      (value "INA169")
      (footprint "eagle-import:SOT23-5")
      (fields (field (name "MANF") "Texas Instruments"))
      (libsource (lib "eagle-import") (part "INA169"))
    )
    (comp (ref "J1")
      (value "CONNECTION-SMD-BIG")
      (footprint "eagle-import:CONNECTION_BIG")
      (libsource (lib "eagle-import") (part "CONNECTION-SMD-BIG"))
    )
    (comp (ref "LED4")
      (value "LED-0603")
      (footprint "eagle-import:LED0603")
      (fields
        (field (name "PACKAGE") "0603")
        (field (name "COLOR") "RED")
        (field (name "LCSC#") "C2286")
        (field (name "MANF") "Hubei KENTO Elec")
        (field (name "MANF#") "KT-0603R")
      )
      (libsource (lib "eagle-import") (part "LED-0603"))
    )
    (comp (ref "M1")
      (value "PAD_PAIR-4X10")
      (footprint "eagle-import:4X10_PAIR")
      (libsource (lib "eagle-import") (part "PAD_PAIR-4X10"))
    )
    (comp (ref "M2")
      (value "PAD_PAIR-4X10")
      (footprint "eagle-import:4X10_PAIR")
      (libsource (lib "eagle-import") (part "PAD_PAIR-4X10"))
    )
    (comp (ref "M3")
      (value "PAD_PAIR-4X10")
      (footprint "eagle-import:4X10_PAIR")
      (libsource (lib "eagle-import") (part "PAD_PAIR-4X10"))
    )
    (comp (ref "M4")
      (value "PAD_PAIR-4X10")
      (footprint "eagle-import:4X10_PAIR")
      (libsource (lib "eagle-import") (part "PAD_PAIR-4X10"))
    )
    (comp (ref "M5")
      (value "PAD_PAIR-4X10")
      (footprint "eagle-import:4X10_PAIR")
      (libsource (lib "eagle-import") (part "PAD_PAIR-4X10"))
    )
    (comp (ref "M6")
      (value "PAD_PAIR-4X10")
      (footprint "eagle-import:4X10_PAIR")
      (libsource (lib "eagle-import") (part "PAD_PAIR-4X10"))
    )
    (comp (ref "PAD1")
      (value "PAD-10X4")
      (footprint "eagle-import:10X4")
      (libsource (lib "eagle-import") (part "PAD-10X4"))
    )
    (comp (ref "PAD2")
      (value "PAD-10X4")
      (footprint "eagle-import:10X4")
      (libsource (lib "eagle-import") (part "PAD-10X4"))
    )
    (comp (ref "PAD5")
      (value "PAD-10X4")
      (footprint "eagle-import:10X4")
      (libsource (lib "eagle-import") (part "PAD-10X4"))
    )
    (comp (ref "PAD6")
      (value "PAD-10X4")
      (footprint "eagle-import:10X4")
      (libsource (lib "eagle-import") (part "PAD-10X4"))
    )
    (comp (ref "PAD7")
      (value "PAD-10X4")
      (footprint "eagle-import:10X4")
      (libsource (lib "eagle-import") (part "PAD-10X4"))
    )
    (comp (ref "PAD10")
      (value "PAD-10X4")
      (footprint "eagle-import:10X4")
      (libsource (lib "eagle-import") (part "PAD-10X4"))
    )
    (comp (ref "PAD28")
      (value "PAD_PAIR-2X6")
      (footprint "eagle-import:2X6_PAIR")
      (libsource (lib "eagle-import") (part "PAD_PAIR-2X6"))
    )
    (comp (ref "PAD29")
      (value "PAD_PAIR-2X6")
      (footprint "eagle-import:2X6_PAIR")
      (libsource (lib "eagle-import") (part "PAD_PAIR-2X6"))
    )
    (comp (ref "PAD30")
      (value "PAD_PAIR-2X6")
      (footprint "eagle-import:2X6_PAIR")
      (libsource (lib "eagle-import") (part "PAD_PAIR-2X6"))
    )
    (comp (ref "PAD31")
      (value "PAD_PAIR-2X6")
      (footprint "eagle-import:2X6_PAIR")
      (libsource (lib "eagle-import") (part "PAD_PAIR-2X6"))
    )
    (comp (ref "PAD32")
      (value "PAD_PAIR-2X6")
      (footprint "eagle-import:2X6_PAIR")
      (libsource (lib "eagle-import") (part "PAD_PAIR-2X6"))
    )
    (comp (ref "PAD33")
      (value "PAD_PAIR-2X6")
      (footprint "eagle-import:2X6_PAIR")
      (libsource (lib "eagle-import") (part "PAD_PAIR-2X6"))
    )
    (comp (ref "Q1")
      (value "IRLML0030")
      (footprint "eagle-import:SOT23")
      (fields
        (field (name "MANF#") "IRLML0030TRPBF")
        (field (name "PACKAGE") "SOT23")
        (field (name "MANF") "Infineon Technologies")
      )
      (libsource (lib "eagle-import") (part "IRLML0030"))
    )
    (comp (ref "Q2")
      (value "IRFR2407PBF")
      (footprint "eagle-import:D-PAK")
      (fields
        (field (name "MANF#") "IRFR2407PBF")
        (field (name "PACKAGE") "DPak")
        (field (name "MANF") "International Rectifier")
      )
      (libsource (lib "eagle-import") (part "IRFR2407PBF"))
    )
    (comp (ref "Q2_")
      (value "IRFH5010TRPBF-DFN5X6")
      (footprint "eagle-import:PG-TDSON-8")
      (fields
        (field (name "MANF#") "IRFH5010TRPBF")
        (field (name "PACKAGE") "PQFN(5x6)")
        (field (name "MANF") "Infineon")
      )
      (libsource (lib "eagle-import") (part "IRFH5010TRPBF-DFN5X6"))
    )
    (comp (ref "Q3")
      (value "IRFR2407PBF")
      (footprint "eagle-import:D-PAK")
      (fields
        (field (name "MANF#") "IRFR2407PBF")
        (field (name "PACKAGE") "DPak")
        (field (name "MANF") "International Rectifier")
      )
      (libsource (lib "eagle-import") (part "IRFR2407PBF"))
    )
    (comp (ref "Q3_")
      (value "IRFH5010TRPBF-DFN5X6")
      (footprint "eagle-import:PG-TDSON-8")
      (fields
        (field (name "MANF#") "IRFH5010TRPBF")
        (field (name "PACKAGE") "PQFN(5x6)")
        (field (name "MANF") "Infineon")
      )
      (libsource (lib "eagle-import") (part "IRFH5010TRPBF-DFN5X6"))
    )
    (comp (ref "Q4")
      (value "IRFR2407PBF")
      (footprint "eagle-import:D-PAK")
      (fields
        (field (name "MANF#") "IRFR2407PBF")
        (field (name "PACKAGE") "DPak")
        (field (name "MANF") "International Rectifier")
      )
      (libsource (lib "eagle-import") (part "IRFR2407PBF"))
    )
    (comp (ref "Q4_")
      (value "IRFH5010TRPBF-DFN5X6")
      (footprint "eagle-import:PG-TDSON-8")
      (fields
        (field (name "MANF#") "IRFH5010TRPBF")
        (field (name "PACKAGE") "PQFN(5x6)")
        (field (name "MANF") "Infineon")
      )
      (libsource (lib "eagle-import") (part "IRFH5010TRPBF-DFN5X6"))
    )
    (comp (ref "R1")
      (value "120R")
      (footprint "eagle-import:R0603")
      (fields
        (field (name "PACKAGE") "0603")
        (field (name "TOLERANCE") "1%")
        (field (name "ALLOCATED") "+")
        (field (name "LCSC#") "C22787")
        (field (name "MANF") "UNI-ROYAL(Uniroyal Elec)")
        (field (name "MANF#") "0603WAF1200T5E")
      )
      (libsource (lib "eagle-import") (part "R-0603-1%"))
    )
    (comp (ref "R2")
      (value "120R")
      (footprint "eagle-import:R0603")
      (fields
        (field (name "PACKAGE") "0603")
        (field (name "TOLERANCE") "1%")
        (field (name "ALLOCATED") "+")
        (field (name "LCSC#") "C22787")
        (field (name "MANF") "UNI-ROYAL(Uniroyal Elec)")
        (field (name "MANF#") "0603WAF1200T5E")
      )
      (libsource (lib "eagle-import") (part "R-0603-1%"))
    )
    (comp (ref "R3")
      (value "82K")
      (footprint "eagle-import:R0603")
      (fields
        (field (name "PACKAGE") "0603")
        (field (name "TOLERANCE") "1%")
        (field (name "ALLOCATED") "+")
        (field (name "LCSC#") "C23254")
        (field (name "MANF") "UNI-ROYAL(Uniroyal Elec)")
        (field (name "MANF#") "0603WAF8202T5E")
      )
      (libsource (lib "eagle-import") (part "R-0603-1%"))
    )
    (comp (ref "R4")
      (value "200 µOhms")
      (footprint "eagle-import:R3920-KELVIN")
      (fields
        (field (name "MANF") "Bourns Inc")
        (field (name "POWER") "12W")
        (field (name "TOLERANCE") "±1%")
      )
      (libsource (lib "eagle-import") (part "CURRENT_SHUNT_KELVIN-3920-KELVIN-0.0002R"))
    )
    (comp (ref "R13")
      (value "10K2")
      (footprint "eagle-import:R0603")
      (fields
        (field (name "PACKAGE") "0603")
        (field (name "TOLERANCE") "1%")
        (field (name "ALLOCATED") "+")
        (field (name "LCSC#") "C22772")
        (field (name "MANF") "UNI-ROYAL(Uniroyal Elec)")
        (field (name "MANF#") "0603WAF1022T5E")
      )
      (libsource (lib "eagle-import") (part "R-0603-1%"))
    )
    (comp (ref "R14")
      (value "82K")
      (footprint "eagle-import:R0603")
      (fields
        (field (name "PACKAGE") "0603")
        (field (name "TOLERANCE") "1%")
        (field (name "ALLOCATED") "+")
        (field (name "LCSC#") "C23254")
        (field (name "MANF") "UNI-ROYAL(Uniroyal Elec)")
        (field (name "MANF#") "0603WAF8202T5E")
      )
      (libsource (lib "eagle-import") (part "R-0603-1%"))
    )
    (comp (ref "R15")
      (value "82K")
      (footprint "eagle-import:R0603")
      (fields
        (field (name "PACKAGE") "0603")
        (field (name "TOLERANCE") "1%")
        (field (name "ALLOCATED") "+")
        (field (name "LCSC#") "C23254")
        (field (name "MANF") "UNI-ROYAL(Uniroyal Elec)")
        (field (name "MANF#") "0603WAF8202T5E")
      )
      (libsource (lib "eagle-import") (part "R-0603-1%"))
    )
    (comp (ref "R18")
      (value "1K")
      (footprint "eagle-import:R0603")
      (fields
        (field (name "PACKAGE") "0603")
        (field (name "TOLERANCE") "1%")
        (field (name "ALLOCATED") "+")
        (field (name "LCSC#") "C21190")
        (field (name "MANF") "UNI-ROYAL(Uniroyal Elec)")
        (field (name "MANF#") "0603WAF1001T5E")
      )
      (libsource (lib "eagle-import") (part "R-0603-1%"))
    )
    (comp (ref "R20")
      (value "200R")
      (footprint "eagle-import:R0603")
      (fields
        (field (name "PACKAGE") "0603")
        (field (name "TOLERANCE") "1%")
        (field (name "ALLOCATED") "+")
        (field (name "LCSC#") "C21190")
        (field (name "MANF") "UNI-ROYAL(Uniroyal Elec)")
        (field (name "MANF#") "0603WAF1001T5E")
      )
      (libsource (lib "eagle-import") (part "R-0603-1%"))
    )
    (comp (ref "R21")
      (value "143K")
      (footprint "eagle-import:R0603")
      (fields
        (field (name "PACKAGE") "0603")
        (field (name "TOLERANCE") "1%")
        (field (name "ALLOCATED") "+")
        (field (name "LCSC#") "C22877")
        (field (name "MANF") "UNI-ROYAL(Uniroyal Elec)")
        (field (name "MANF#") "0603WAF1433T5E")
      )
      (libsource (lib "eagle-import") (part "R-0603-1%"))
    )
    (comp (ref "R22")
      (value "200R")
      (footprint "eagle-import:R1206")
      (fields
        (field (name "PACKAGE") "1206")
        (field (name "TOLERANCE") "1%")
        (field (name "ALLOCATED") "+")
        (field (name "LCSC#") "C25361")
        (field (name "MANF") "UNI-ROYAL")
        (field (name "MANF#") "1206W4J0201T5E")
      )
      (libsource (lib "eagle-import") (part "R-1206-1%"))
    )
    (comp (ref "R23")
      (value "DNM")
      (footprint "eagle-import:R1206")
      (fields (field (name "PACKAGE") "1206") (field (name "TOLERANCE") "1%"))
      (libsource (lib "eagle-import") (part "R-1206-1%"))
    )
    (comp (ref "R24")
      (value "143K")
      (footprint "eagle-import:R0603")
      (fields
        (field (name "PACKAGE") "0603")
        (field (name "TOLERANCE") "1%")
        (field (name "ALLOCATED") "+")
        (field (name "LCSC#") "C22877")
        (field (name "MANF") "UNI-ROYAL(Uniroyal Elec)")
        (field (name "MANF#") "0603WAF1433T5E")
      )
      (libsource (lib "eagle-import") (part "R-0603-1%"))
    )
    (comp (ref "SJ2")
      (value "SOLDER_JOINT-SJ1")
      (footprint "eagle-import:RES_0")
      (libsource (lib "eagle-import") (part "SOLDER_JOINT-SJ1"))
    )
    (comp (ref "ZD1")
      (value "MM3Z12VBW")
      (footprint "eagle-import:SOD323")
      (fields (field (name "MANF#") "MM3Z12VBW") (field (name "MANF") "Tak Cheong"))
      (libsource (lib "eagle-import") (part "MM3Z12VBW"))
    )
  )
  (nets
    (net (code "1") (name "ALARM") (class "Default")
      (node (ref "CON1") (pin "24") (pinfunction "ALARM_24") (pintype "bidirectional"))
      (node (ref "R20") (pin "2") (pinfunction "2_2") (pintype "passive"))
    )
    (net (code "2") (name "BAT1-") (class "Default")
      (node (ref "BAT1PAD2") (pin "2") (pinfunction "P$1_2") (pintype "bidirectional"))
      (node (ref "Q4") (pin "D") (pinfunction "D_D") (pintype "passive"))
      (node (ref "Q4_") (pin "5D") (pinfunction "D_5D") (pintype "passive"))
      (node (ref "Q4_") (pin "6D") (pinfunction "D_6D") (pintype "passive"))
      (node (ref "Q4_") (pin "7D") (pinfunction "D_7D") (pintype "passive"))
      (node (ref "Q4_") (pin "8D") (pinfunction "D_8D") (pintype "passive"))
      (node (ref "Q4_") (pin "PAD_D") (pinfunction "D_PAD_D") (pintype "passive"))
    )
    (net (code "3") (name "BAT1_MID") (class "Default")
      (node (ref "BAT1PAD2") (pin "1") (pinfunction "P$1_1") (pintype "bidirectional"))
      (node (ref "PAD7") (pin "P$1") (pinfunction "P$1_P$1") (pintype "bidirectional"))
    )
    (net (code "4") (name "BAT2-") (class "Default")
      (node (ref "BAT2PAD2") (pin "2") (pinfunction "P$1_2") (pintype "bidirectional"))
      (node (ref "Q3") (pin "D") (pinfunction "D_D") (pintype "passive"))
      (node (ref "Q3_") (pin "5D") (pinfunction "D_5D") (pintype "passive"))
      (node (ref "Q3_") (pin "6D") (pinfunction "D_6D") (pintype "passive"))
      (node (ref "Q3_") (pin "7D") (pinfunction "D_7D") (pintype "passive"))
      (node (ref "Q3_") (pin "8D") (pinfunction "D_8D") (pintype "passive"))
      (node (ref "Q3_") (pin "PAD_D") (pinfunction "D_PAD_D") (pintype "passive"))
    )
    (net (code "5") (name "BAT2_MID") (class "Default")
      (node (ref "BAT2PAD2") (pin "1") (pinfunction "P$1_1") (pintype "bidirectional"))
      (node (ref "PAD2") (pin "P$1") (pinfunction "P$1_P$1") (pintype "bidirectional"))
    )
    (net (code "6") (name "BAT3-") (class "Default")
      (node (ref "BAT3PAD2") (pin "2") (pinfunction "P$1_2") (pintype "bidirectional"))
      (node (ref "Q2") (pin "D") (pinfunction "D_D") (pintype "passive"))
      (node (ref "Q2_") (pin "5D") (pinfunction "D_5D") (pintype "passive"))
      (node (ref "Q2_") (pin "6D") (pinfunction "D_6D") (pintype "passive"))
      (node (ref "Q2_") (pin "7D") (pinfunction "D_7D") (pintype "passive"))
      (node (ref "Q2_") (pin "8D") (pinfunction "D_8D") (pintype "passive"))
      (node (ref "Q2_") (pin "PAD_D") (pinfunction "D_PAD_D") (pintype "passive"))
    )
    (net (code "7") (name "BAT3_MID") (class "Default")
      (node (ref "BAT3PAD2") (pin "1") (pinfunction "P$1_1") (pintype "bidirectional"))
      (node (ref "PAD6") (pin "P$1") (pinfunction "P$1_P$1") (pintype "bidirectional"))
    )
    (net (code "8") (name "BATT_CURRENT_SENS_PROT") (class "Default")
      (node (ref "C3") (pin "2") (pinfunction "2_2") (pintype "passive"))
      (node (ref "CON1") (pin "49") (pinfunction "BATT_CURRENT_SENS_PROT_49") (pintype "bidirectional"))
      (node (ref "IC1") (pin "1") (pinfunction "OUT_1") (pintype "bidirectional"))
      (node (ref "R3") (pin "2") (pinfunction "2_2") (pintype "passive"))
    )
    (net (code "9") (name "BATT_VOLTAGE_SENS_PROT") (class "Default")
      (node (ref "C4") (pin "2") (pinfunction "2_2") (pintype "passive"))
      (node (ref "CON1") (pin "47") (pinfunction "BATT_VOLTAGE_SENS_PROT_47") (pintype "bidirectional"))
      (node (ref "R13") (pin "2") (pinfunction "2_2") (pintype "passive"))
      (node (ref "R15") (pin "1") (pinfunction "1_1") (pintype "passive"))
    )
    (net (code "10") (name "CAN1_H") (class "Default")
      (node (ref "CON1") (pin "79") (pinfunction "CAN1_H_79") (pintype "bidirectional"))
      (node (ref "CON20") (pin "2") (pinfunction "2_2") (pintype "bidirectional"))
      (node (ref "R2") (pin "1") (pinfunction "1_1") (pintype "passive"))
    )
    (net (code "11") (name "CAN1_L") (class "Default")
      (node (ref "CON1") (pin "77") (pinfunction "CAN1_L_77") (pintype "bidirectional"))
      (node (ref "CON20") (pin "3") (pinfunction "3_3") (pintype "bidirectional"))
      (node (ref "SJ2") (pin "2") (pinfunction "2_2") (pintype "passive"))
    )
    (net (code "12") (name "CAN2_H") (class "Default")
      (node (ref "CON1") (pin "41") (pinfunction "CAN2_H_41") (pintype "bidirectional"))
      (node (ref "CON10") (pin "2") (pinfunction "2_2") (pintype "bidirectional"))
      (node (ref "CON11") (pin "2") (pinfunction "2_2") (pintype "bidirectional"))
      (node (ref "CON12") (pin "2") (pinfunction "2_2") (pintype "bidirectional"))
      (node (ref "CON21") (pin "2") (pinfunction "2_2") (pintype "bidirectional"))
      (node (ref "CON6") (pin "2") (pinfunction "2_2") (pintype "bidirectional"))
      (node (ref "CON7") (pin "2") (pinfunction "2_2") (pintype "bidirectional"))
      (node (ref "CON8") (pin "2") (pinfunction "2_2") (pintype "bidirectional"))
      (node (ref "CON9") (pin "2") (pinfunction "2_2") (pintype "bidirectional"))
      (node (ref "R1") (pin "1") (pinfunction "1_1") (pintype "passive"))
    )
    (net (code "13") (name "CAN2_L") (class "Default")
      (node (ref "CON1") (pin "39") (pinfunction "CAN2_L_39") (pintype "bidirectional"))
      (node (ref "CON10") (pin "3") (pinfunction "3_3") (pintype "bidirectional"))
      (node (ref "CON11") (pin "3") (pinfunction "3_3") (pintype "bidirectional"))
      (node (ref "CON12") (pin "3") (pinfunction "3_3") (pintype "bidirectional"))
      (node (ref "CON21") (pin "3") (pinfunction "3_3") (pintype "bidirectional"))
      (node (ref "CON6") (pin "3") (pinfunction "3_3") (pintype "bidirectional"))
      (node (ref "CON7") (pin "3") (pinfunction "3_3") (pintype "bidirectional"))
      (node (ref "CON8") (pin "3") (pinfunction "3_3") (pintype "bidirectional"))
      (node (ref "CON9") (pin "3") (pinfunction "3_3") (pintype "bidirectional"))
      (node (ref "R1") (pin "2") (pinfunction "2_2") (pintype "passive"))
    )
    (net (code "14") (name "ETH_RX+") (class "Default")
      (node (ref "CON18") (pin "2") (pinfunction "2_2") (pintype "passive"))
      (node (ref "CON22") (pin "2") (pinfunction "2_2") (pintype "passive"))
      (node (ref "CON5") (pin "2") (pinfunction "2_2") (pintype "bidirectional"))
    )
    (net (code "15") (name "ETH_RX-") (class "Default")
      (node (ref "CON18") (pin "1") (pinfunction "1_1") (pintype "passive"))
      (node (ref "CON22") (pin "1") (pinfunction "1_1") (pintype "passive"))
      (node (ref "CON5") (pin "1") (pinfunction "1_1") (pintype "bidirectional"))
    )
    (net (code "16") (name "ETH_TX+") (class "Default")
      (node (ref "CON18") (pin "4") (pinfunction "4_4") (pintype "passive"))
      (node (ref "CON22") (pin "4") (pinfunction "4_4") (pintype "passive"))
      (node (ref "CON5") (pin "4") (pinfunction "4_4") (pintype "bidirectional"))
    )
    (net (code "17") (name "ETH_TX-") (class "Default")
      (node (ref "CON18") (pin "3") (pinfunction "3_3") (pintype "passive"))
      (node (ref "CON22") (pin "3") (pinfunction "3_3") (pintype "passive"))
      (node (ref "CON5") (pin "3") (pinfunction "3_3") (pintype "bidirectional"))
    )
    (net (code "18") (name "ETH_UART_RX") (class "Default")
      (node (ref "CON18") (pin "6") (pinfunction "6_6") (pintype "passive"))
      (node (ref "CON22") (pin "6") (pinfunction "6_6") (pintype "passive"))
    )
    (net (code "19") (name "ETH_UART_TX") (class "Default")
      (node (ref "CON18") (pin "5") (pinfunction "5_5") (pintype "passive"))
      (node (ref "CON22") (pin "5") (pinfunction "5_5") (pintype "passive"))
    )
    (net (code "20") (name "FMU-CH1-PROT{slash}MOTOR1") (class "Default")
      (node (ref "CON1") (pin "50") (pinfunction "FMU-CH1-PROT_50") (pintype "bidirectional"))
      (node (ref "PAD28") (pin "2") (pinfunction "P$1_2") (pintype "bidirectional"))
    )
    (net (code "21") (name "FMU-CH2-PROT{slash}MOTOR2") (class "Default")
      (node (ref "CON1") (pin "52") (pinfunction "FMU-CH2-PROT_52") (pintype "bidirectional"))
      (node (ref "PAD29") (pin "2") (pinfunction "P$1_2") (pintype "bidirectional"))
    )
    (net (code "22") (name "FMU-CH3-PROT{slash}MOTOR3") (class "Default")
      (node (ref "CON1") (pin "54") (pinfunction "FMU-CH3-PROT_54") (pintype "bidirectional"))
      (node (ref "PAD30") (pin "2") (pinfunction "P$1_2") (pintype "bidirectional"))
    )
    (net (code "23") (name "FMU-CH4-PROT{slash}MOTOR4") (class "Default")
      (node (ref "CON1") (pin "56") (pinfunction "FMU-CH4-PROT_56") (pintype "bidirectional"))
      (node (ref "PAD31") (pin "2") (pinfunction "P$1_2") (pintype "bidirectional"))
    )
    (net (code "24") (name "FMU-CH5-PROT{slash}MOTOR5") (class "Default")
      (node (ref "CON1") (pin "58") (pinfunction "FMU-CH5-PROT_58") (pintype "bidirectional"))
      (node (ref "PAD32") (pin "2") (pinfunction "P$1_2") (pintype "bidirectional"))
    )
    (net (code "25") (name "FMU-CH6-PROT{slash}MOTOR6") (class "Default")
      (node (ref "CON1") (pin "60") (pinfunction "FMU-CH6-PROT_60") (pintype "bidirectional"))
      (node (ref "PAD33") (pin "2") (pinfunction "P$1_2") (pintype "bidirectional"))
    )
    (net (code "26") (name "GND") (class "Default")
      (node (ref "C1") (pin "1") (pinfunction "1_1") (pintype "passive"))
      (node (ref "C11") (pin "1") (pinfunction "1_1") (pintype "passive"))
      (node (ref "C12") (pin "1") (pinfunction "1_1") (pintype "passive"))
      (node (ref "C13") (pin "1") (pinfunction "1_1") (pintype "passive"))
      (node (ref "C14") (pin "1") (pinfunction "1_1") (pintype "passive"))
      (node (ref "C15") (pin "1") (pinfunction "1_1") (pintype "passive"))
      (node (ref "C16") (pin "P$1") (pinfunction "1_P$1") (pintype "passive"))
      (node (ref "C17") (pin "P$1") (pinfunction "1_P$1") (pintype "passive"))
      (node (ref "C18") (pin "P$1") (pinfunction "1_P$1") (pintype "passive"))
      (node (ref "C3") (pin "1") (pinfunction "1_1") (pintype "passive"))
      (node (ref "C38") (pin "1") (pinfunction "1_1") (pintype "passive"))
      (node (ref "C39") (pin "1") (pinfunction "1_1") (pintype "passive"))
      (node (ref "C4") (pin "1") (pinfunction "1_1") (pintype "passive"))
      (node (ref "C40") (pin "1") (pinfunction "1_1") (pintype "passive"))
      (node (ref "C41") (pin "1") (pinfunction "1_1") (pintype "passive"))
      (node (ref "C42") (pin "1") (pinfunction "1_1") (pintype "passive"))
      (node (ref "C43") (pin "1") (pinfunction "1_1") (pintype "passive"))
      (node (ref "C44") (pin "1") (pinfunction "1_1") (pintype "passive"))
      (node (ref "C45") (pin "1") (pinfunction "1_1") (pintype "passive"))
      (node (ref "C56") (pin "1") (pinfunction "1_1") (pintype "passive"))
      (node (ref "C57") (pin "1") (pinfunction "1_1") (pintype "passive"))
      (node (ref "C58") (pin "1") (pinfunction "1_1") (pintype "passive"))
      (node (ref "C59") (pin "1") (pinfunction "1_1") (pintype "passive"))
      (node (ref "C60") (pin "1") (pinfunction "1_1") (pintype "passive"))
      (node (ref "C61") (pin "1") (pinfunction "1_1") (pintype "passive"))
      (node (ref "C62") (pin "1") (pinfunction "1_1") (pintype "passive"))
      (node (ref "C63") (pin "1") (pinfunction "1_1") (pintype "passive"))
      (node (ref "CON1") (pin "13") (pinfunction "GND_13") (pintype "bidirectional"))
      (node (ref "CON1") (pin "15") (pinfunction "GND_15") (pintype "bidirectional"))
      (node (ref "CON1") (pin "55") (pinfunction "~{VDD_BRICK_VALID\\}_55") (pintype "bidirectional"))
      (node (ref "CON10") (pin "4") (pinfunction "4_4") (pintype "bidirectional"))
      (node (ref "CON10") (pin "M$0") (pinfunction "GND_M$0") (pintype "bidirectional"))
      (node (ref "CON10") (pin "M$1") (pinfunction "GND_M$1") (pintype "bidirectional"))
      (node (ref "CON11") (pin "4") (pinfunction "4_4") (pintype "bidirectional"))
      (node (ref "CON11") (pin "M$0") (pinfunction "GND_M$0") (pintype "bidirectional"))
      (node (ref "CON11") (pin "M$1") (pinfunction "GND_M$1") (pintype "bidirectional"))
      (node (ref "CON12") (pin "4") (pinfunction "4_4") (pintype "bidirectional"))
      (node (ref "CON12") (pin "M$0") (pinfunction "GND_M$0") (pintype "bidirectional"))
      (node (ref "CON12") (pin "M$1") (pinfunction "GND_M$1") (pintype "bidirectional"))
      (node (ref "CON13") (pin "1") (pinfunction "1_1") (pintype "bidirectional"))
      (node (ref "CON13") (pin "M$0") (pinfunction "GND_M$0") (pintype "bidirectional"))
      (node (ref "CON13") (pin "M$1") (pinfunction "GND_M$1") (pintype "bidirectional"))
      (node (ref "CON14") (pin "1") (pinfunction "1_1") (pintype "passive"))
      (node (ref "CON15") (pin "1") (pinfunction "1_1") (pintype "passive"))
      (node (ref "CON16") (pin "1") (pinfunction "1_1") (pintype "passive"))
      (node (ref "CON16") (pin "M$0") (pinfunction "G1_M$0") (pintype "passive"))
      (node (ref "CON16") (pin "M$1") (pinfunction "G1_M$1") (pintype "passive"))
      (node (ref "CON17") (pin "1") (pinfunction "1_1") (pintype "bidirectional"))
      (node (ref "CON17") (pin "M$0") (pinfunction "GND_M$0") (pintype "bidirectional"))
      (node (ref "CON17") (pin "M$1") (pinfunction "GND_M$1") (pintype "bidirectional"))
      (node (ref "CON18") (pin "12") (pinfunction "12_12") (pintype "passive"))
      (node (ref "CON18") (pin "13") (pinfunction "13_13") (pintype "passive"))
      (node (ref "CON18") (pin "14") (pinfunction "14_14") (pintype "passive"))
      (node (ref "CON18") (pin "M$0") (pinfunction "G1_M$0") (pintype "passive"))
      (node (ref "CON18") (pin "M$1") (pinfunction "G1_M$1") (pintype "passive"))
      (node (ref "CON19") (pin "A1") (pinfunction "GND_A1") (pintype "bidirectional"))
      (node (ref "CON19") (pin "A12") (pinfunction "GND_A12") (pintype "bidirectional"))
      (node (ref "CON19") (pin "B1") (pinfunction "GND_B1") (pintype "bidirectional"))
      (node (ref "CON19") (pin "B12") (pinfunction "GND_B12") (pintype "bidirectional"))
      (node (ref "CON19") (pin "G1") (pinfunction "GND_G1") (pintype "bidirectional"))
      (node (ref "CON19") (pin "G10") (pinfunction "GND_G10") (pintype "bidirectional"))
      (node (ref "CON19") (pin "G2") (pinfunction "GND_G2") (pintype "bidirectional"))
      (node (ref "CON19") (pin "G4") (pinfunction "GND_G4") (pintype "bidirectional"))
      (node (ref "CON19") (pin "G5") (pinfunction "GND_G5") (pintype "bidirectional"))
      (node (ref "CON19") (pin "G7") (pinfunction "GND_G7") (pintype "bidirectional"))
      (node (ref "CON19") (pin "G8") (pinfunction "GND_G8") (pintype "bidirectional"))
      (node (ref "CON19") (pin "G9") (pinfunction "GND_G9") (pintype "bidirectional"))
      (node (ref "CON19") (pin "P$1") (pinfunction "GND_P$1") (pintype "bidirectional"))
      (node (ref "CON19") (pin "P$2") (pinfunction "GND_P$2") (pintype "bidirectional"))
      (node (ref "CON2") (pin "1") (pinfunction "1_1") (pintype "bidirectional"))
      (node (ref "CON2") (pin "M$0") (pinfunction "GND_M$0") (pintype "bidirectional"))
      (node (ref "CON2") (pin "M$1") (pinfunction "GND_M$1") (pintype "bidirectional"))
      (node (ref "CON20") (pin "4") (pinfunction "4_4") (pintype "bidirectional"))
      (node (ref "CON20") (pin "M$0") (pinfunction "GND_M$0") (pintype "bidirectional"))
      (node (ref "CON20") (pin "M$1") (pinfunction "GND_M$1") (pintype "bidirectional"))
      (node (ref "CON21") (pin "4") (pinfunction "4_4") (pintype "bidirectional"))
      (node (ref "CON21") (pin "M$0") (pinfunction "GND_M$0") (pintype "bidirectional"))
      (node (ref "CON21") (pin "M$1") (pinfunction "GND_M$1") (pintype "bidirectional"))
      (node (ref "CON22") (pin "12") (pinfunction "12_12") (pintype "passive"))
      (node (ref "CON22") (pin "13") (pinfunction "13_13") (pintype "passive"))
      (node (ref "CON22") (pin "14") (pinfunction "14_14") (pintype "passive"))
      (node (ref "CON22") (pin "M$0") (pinfunction "G1_M$0") (pintype "passive"))
      (node (ref "CON22") (pin "M$1") (pinfunction "G1_M$1") (pintype "passive"))
      (node (ref "CON24") (pin "3") (pinfunction "3_3") (pintype "bidirectional"))
      (node (ref "CON24") (pin "4") (pinfunction "4_4") (pintype "bidirectional"))
      (node (ref "CON24") (pin "M$0") (pinfunction "GND_M$0") (pintype "bidirectional"))
      (node (ref "CON24") (pin "M$1") (pinfunction "GND_M$1") (pintype "bidirectional"))
      (node (ref "CON3") (pin "1") (pinfunction "1_1") (pintype "bidirectional"))
      (node (ref "CON3") (pin "4") (pinfunction "4_4") (pintype "bidirectional"))
      (node (ref "CON3") (pin "M$0") (pinfunction "GND_M$0") (pintype "bidirectional"))
      (node (ref "CON3") (pin "M$1") (pinfunction "GND_M$1") (pintype "bidirectional"))
      (node (ref "CON4") (pin "1") (pinfunction "1_1") (pintype "bidirectional"))
      (node (ref "CON4") (pin "M$0") (pinfunction "GND_M$0") (pintype "bidirectional"))
      (node (ref "CON4") (pin "M$1") (pinfunction "GND_M$1") (pintype "bidirectional"))
      (node (ref "CON5") (pin "M$0") (pinfunction "GND_M$0") (pintype "bidirectional"))
      (node (ref "CON5") (pin "M$1") (pinfunction "GND_M$1") (pintype "bidirectional"))
      (node (ref "CON6") (pin "4") (pinfunction "4_4") (pintype "bidirectional"))
      (node (ref "CON6") (pin "M$0") (pinfunction "GND_M$0") (pintype "bidirectional"))
      (node (ref "CON6") (pin "M$1") (pinfunction "GND_M$1") (pintype "bidirectional"))
      (node (ref "CON7") (pin "4") (pinfunction "4_4") (pintype "bidirectional"))
      (node (ref "CON7") (pin "M$0") (pinfunction "GND_M$0") (pintype "bidirectional"))
      (node (ref "CON7") (pin "M$1") (pinfunction "GND_M$1") (pintype "bidirectional"))
      (node (ref "CON8") (pin "4") (pinfunction "4_4") (pintype "bidirectional"))
      (node (ref "CON8") (pin "M$0") (pinfunction "GND_M$0") (pintype "bidirectional"))
      (node (ref "CON8") (pin "M$1") (pinfunction "GND_M$1") (pintype "bidirectional"))
      (node (ref "CON9") (pin "4") (pinfunction "4_4") (pintype "bidirectional"))
      (node (ref "CON9") (pin "M$0") (pinfunction "GND_M$0") (pintype "bidirectional"))
      (node (ref "CON9") (pin "M$1") (pinfunction "GND_M$1") (pintype "bidirectional"))
      (node (ref "D2") (pin "A") (pinfunction "A_A") (pintype "passive"))
      (node (ref "D5") (pin "A") (pinfunction "A_A") (pintype "passive"))
      (node (ref "D7") (pin "A") (pinfunction "A_A") (pintype "passive"))
      (node (ref "IC1") (pin "2") (pinfunction "GND_2") (pintype "bidirectional"))
      (node (ref "IC2") (pin "7") (pinfunction "GND_7") (pintype "bidirectional"))
      (node (ref "IC2") (pin "P$1") (pinfunction "GND_P$1") (pintype "bidirectional"))
      (node (ref "IC5") (pin "7") (pinfunction "GND_7") (pintype "bidirectional"))
      (node (ref "IC5") (pin "P$1") (pinfunction "GND_P$1") (pintype "bidirectional"))
      (node (ref "IC7") (pin "7") (pinfunction "GND_7") (pintype "bidirectional"))
      (node (ref "IC7") (pin "P$1") (pinfunction "GND_P$1") (pintype "bidirectional"))
      (node (ref "J1") (pin "1") (pinfunction "P$1_1") (pintype "bidirectional"))
      (node (ref "LED1") (pin "C") (pinfunction "C_C") (pintype "bidirectional"))
      (node (ref "LED2") (pin "C") (pinfunction "C_C") (pintype "bidirectional"))
      (node (ref "LED3") (pin "C") (pinfunction "C_C") (pintype "bidirectional"))
      (node (ref "PAD13") (pin "P$1") (pinfunction "P$1_P$1") (pintype "bidirectional"))
      (node (ref "PAD16") (pin "P$1") (pinfunction "P$1_P$1") (pintype "bidirectional"))
      (node (ref "PAD18") (pin "P$1") (pinfunction "P$1_P$1") (pintype "bidirectional"))
      (node (ref "PAD28") (pin "1") (pinfunction "P$1_1") (pintype "bidirectional"))
      (node (ref "PAD29") (pin "1") (pinfunction "P$1_1") (pintype "bidirectional"))
      (node (ref "PAD30") (pin "1") (pinfunction "P$1_1") (pintype "bidirectional"))
      (node (ref "PAD31") (pin "1") (pinfunction "P$1_1") (pintype "bidirectional"))
      (node (ref "PAD32") (pin "1") (pinfunction "P$1_1") (pintype "bidirectional"))
      (node (ref "PAD33") (pin "1") (pinfunction "P$1_1") (pintype "bidirectional"))
      (node (ref "Q1") (pin "2") (pinfunction "S_2") (pintype "passive"))
      (node (ref "R12") (pin "1") (pinfunction "1_1") (pintype "passive"))
      (node (ref "R13") (pin "1") (pinfunction "1_1") (pintype "passive"))
      (node (ref "R17") (pin "1") (pinfunction "1_1") (pintype "passive"))
      (node (ref "R27") (pin "1") (pinfunction "1_1") (pintype "passive"))
      (node (ref "R3") (pin "1") (pinfunction "1_1") (pintype "passive"))
      (node (ref "R30") (pin "1") (pinfunction "1_1") (pintype "passive"))
      (node (ref "R39") (pin "1") (pinfunction "1_1") (pintype "passive"))
      (node (ref "R42") (pin "1") (pinfunction "1_1") (pintype "passive"))
      (node (ref "R9") (pin "1") (pinfunction "1_1") (pintype "passive"))
      (node (ref "ZD1") (pin "A") (pinfunction "A_A") (pintype "passive"))
    )
    (net (code "27") (name "IO-CH1-PROT") (class "Default")
      (node (ref "CON1") (pin "80") (pinfunction "IO-CH1-PROT_80") (pintype "bidirectional"))
      (node (ref "CON16") (pin "2") (pinfunction "2_2") (pintype "passive"))
    )
    (net (code "28") (name "IO-CH2-PROT") (class "Default")
      (node (ref "CON1") (pin "78") (pinfunction "IO-CH2-PROT_78") (pintype "bidirectional"))
      (node (ref "CON16") (pin "3") (pinfunction "3_3") (pintype "passive"))
    )
    (net (code "29") (name "IO-CH3-PROT") (class "Default")
      (node (ref "CON1") (pin "76") (pinfunction "IO-CH3-PROT_76") (pintype "bidirectional"))
      (node (ref "CON16") (pin "4") (pinfunction "4_4") (pintype "passive"))
    )
    (net (code "30") (name "IO-CH4-PROT") (class "Default")
      (node (ref "CON1") (pin "74") (pinfunction "IO-CH4-PROT_74") (pintype "bidirectional"))
      (node (ref "CON16") (pin "5") (pinfunction "5_5") (pintype "passive"))
    )
    (net (code "31") (name "IO-CH5-PROT") (class "Default")
      (node (ref "CON1") (pin "72") (pinfunction "IO-CH5-PROT_72") (pintype "bidirectional"))
      (node (ref "CON16") (pin "6") (pinfunction "6_6") (pintype "passive"))
    )
    (net (code "32") (name "IO-CH7-PROT{slash}24V_EN") (class "Default")
      (node (ref "CON1") (pin "68") (pinfunction "IO-CH7-PROT_68") (pintype "bidirectional"))
      (node (ref "R6") (pin "1") (pinfunction "1_1") (pintype "passive"))
    )
    (net (code "33") (name "IO-CH8-PROT{slash}12V_EN") (class "Default")
      (node (ref "CON1") (pin "66") (pinfunction "IO-CH8-PROT_66") (pintype "bidirectional"))
      (node (ref "R5") (pin "1") (pinfunction "1_1") (pintype "passive"))
    )
    (net (code "34") (name "Net-(BAT1PAD1B-P$1)") (class "Default")
      (node (ref "BAT1PAD1") (pin "2") (pinfunction "P$1_2") (pintype "bidirectional"))
      (node (ref "PAD1") (pin "P$1") (pinfunction "P$1_P$1") (pintype "bidirectional"))
    )
    (net (code "35") (name "Net-(BAT2PAD1B-P$1)") (class "Default")
      (node (ref "BAT2PAD1") (pin "2") (pinfunction "P$1_2") (pintype "bidirectional"))
      (node (ref "PAD5") (pin "P$1") (pinfunction "P$1_P$1") (pintype "bidirectional"))
    )
    (net (code "36") (name "Net-(BAT3PAD1B-P$1)") (class "Default")
      (node (ref "BAT3PAD1") (pin "2") (pinfunction "P$1_2") (pintype "bidirectional"))
      (node (ref "PAD10") (pin "P$1") (pinfunction "P$1_P$1") (pintype "bidirectional"))
    )
    (net (code "37") (name "Net-(BUZ1-+)") (class "Default")
      (node (ref "BUZ1") (pin "1") (pinfunction "+_1") (pintype "bidirectional"))
      (node (ref "R22") (pin "P$1") (pinfunction "1_P$1") (pintype "passive"))
      (node (ref "R23") (pin "P$1") (pinfunction "1_P$1") (pintype "passive"))
    )
    (net (code "38") (name "Net-(BUZ1--)") (class "Default")
      (node (ref "BUZ1") (pin "2") (pinfunction "-_2") (pintype "bidirectional"))
      (node (ref "Q1") (pin "3") (pinfunction "D_3") (pintype "passive"))
    )
    (net (code "39") (name "Net-(C14-Pad2)") (class "Default")
      (node (ref "C14") (pin "2") (pinfunction "2_2") (pintype "passive"))
      (node (ref "R10") (pin "1") (pinfunction "1_1") (pintype "passive"))
    )
    (net (code "40") (name "Net-(C41-Pad2)") (class "Default")
      (node (ref "C41") (pin "2") (pinfunction "2_2") (pintype "passive"))
      (node (ref "R28") (pin "1") (pinfunction "1_1") (pintype "passive"))
    )
    (net (code "41") (name "Net-(C43-Pad2)") (class "Default")
      (node (ref "C43") (pin "2") (pinfunction "2_2") (pintype "passive"))
      (node (ref "C44") (pin "2") (pinfunction "2_2") (pintype "passive"))
      (node (ref "C45") (pin "2") (pinfunction "2_2") (pintype "passive"))
      (node (ref "L5") (pin "2") (pinfunction "2_2") (pintype "bidirectional"))
      (node (ref "PAD14") (pin "P$1") (pinfunction "P$1_P$1") (pintype "bidirectional"))
      (node (ref "R29") (pin "2") (pinfunction "2_2") (pintype "passive"))
      (node (ref "SJ1") (pin "1") (pinfunction "1_1") (pintype "passive"))
    )
    (net (code "42") (name "Net-(C59-Pad2)") (class "Default")
      (node (ref "C59") (pin "2") (pinfunction "2_2") (pintype "passive"))
      (node (ref "R40") (pin "1") (pinfunction "1_1") (pintype "passive"))
    )
    (net (code "43") (name "Net-(CON1-I2C2_SCL)") (class "Default")
      (node (ref "CON1") (pin "6") (pinfunction "I2C2_SCL_6") (pintype "bidirectional"))
      (node (ref "CON15") (pin "3") (pinfunction "3_3") (pintype "passive"))
    )
    (net (code "44") (name "Net-(CON1-I2C2_SDA)") (class "Default")
      (node (ref "CON1") (pin "4") (pinfunction "I2C2_SDA_4") (pintype "bidirectional"))
      (node (ref "CON15") (pin "4") (pinfunction "4_4") (pintype "passive"))
    )
    (net (code "45") (name "Net-(CON1-~{FMU_LED_AMBER})") (class "Default")
      (node (ref "CON1") (pin "2") (pinfunction "~{FMU_LED_AMBER}_2") (pintype "bidirectional"))
      (node (ref "LED4") (pin "C") (pinfunction "C_C") (pintype "bidirectional"))
    )
    (net (code "46") (name "Net-(IC1-VIN+)") (class "Default")
      (node (ref "IC1") (pin "3") (pinfunction "VIN+_3") (pintype "bidirectional"))
      (node (ref "R4") (pin "S1") (pinfunction "S1_S1") (pintype "bidirectional"))
    )
    (net (code "47") (name "Net-(IC1-VIN-)") (class "Default")
      (node (ref "IC1") (pin "4") (pinfunction "VIN-_4") (pintype "bidirectional"))
      (node (ref "R4") (pin "S2") (pinfunction "S2_S2") (pintype "bidirectional"))
    )
    (net (code "48") (name "Net-(IC2-BOOT)") (class "Default")
      (node (ref "C2") (pin "1") (pinfunction "1_1") (pintype "passive"))
      (node (ref "IC2") (pin "1") (pinfunction "BOOT_1") (pintype "bidirectional"))
    )
    (net (code "49") (name "Net-(IC2-COMP)") (class "Default")
      (node (ref "C15") (pin "2") (pinfunction "2_2") (pintype "passive"))
      (node (ref "IC2") (pin "6") (pinfunction "COMP_6") (pintype "bidirectional"))
      (node (ref "R10") (pin "2") (pinfunction "2_2") (pintype "passive"))
    )
    (net (code "50") (name "Net-(IC2-EN)") (class "Default")
      (node (ref "IC2") (pin "3") (pinfunction "EN_3") (pintype "bidirectional"))
      (node (ref "R6") (pin "2") (pinfunction "2_2") (pintype "passive"))
    )
    (net (code "51") (name "Net-(IC2-FB)") (class "Default")
      (node (ref "IC2") (pin "5") (pinfunction "FB_5") (pintype "bidirectional"))
      (node (ref "R11") (pin "1") (pinfunction "1_1") (pintype "passive"))
      (node (ref "R12") (pin "2") (pinfunction "2_2") (pintype "passive"))
      (node (ref "R17") (pin "2") (pinfunction "2_2") (pintype "passive"))
    )
    (net (code "52") (name "Net-(IC2-RT{slash}CLK)") (class "Default")
      (node (ref "IC2") (pin "4") (pinfunction "RT/CLK_4") (pintype "bidirectional"))
      (node (ref "R9") (pin "2") (pinfunction "2_2") (pintype "passive"))
    )
    (net (code "53") (name "Net-(IC2-SW)") (class "Default")
      (node (ref "C2") (pin "2") (pinfunction "2_2") (pintype "passive"))
      (node (ref "D2") (pin "C") (pinfunction "C_C") (pintype "passive"))
      (node (ref "IC2") (pin "8") (pinfunction "SW_8") (pintype "bidirectional"))
      (node (ref "L4") (pin "1") (pinfunction "1_1") (pintype "bidirectional"))
    )
    (net (code "54") (name "Net-(IC5-BOOT)") (class "Default")
      (node (ref "C37") (pin "1") (pinfunction "1_1") (pintype "passive"))
      (node (ref "IC5") (pin "1") (pinfunction "BOOT_1") (pintype "bidirectional"))
    )
    (net (code "55") (name "Net-(IC5-COMP)") (class "Default")
      (node (ref "C42") (pin "2") (pinfunction "2_2") (pintype "passive"))
      (node (ref "IC5") (pin "6") (pinfunction "COMP_6") (pintype "bidirectional"))
      (node (ref "R28") (pin "2") (pinfunction "2_2") (pintype "passive"))
    )
    (net (code "56") (name "Net-(IC5-FB)") (class "Default")
      (node (ref "IC5") (pin "5") (pinfunction "FB_5") (pintype "bidirectional"))
      (node (ref "R29") (pin "1") (pinfunction "1_1") (pintype "passive"))
      (node (ref "R30") (pin "2") (pinfunction "2_2") (pintype "passive"))
    )
    (net (code "57") (name "Net-(IC5-RT{slash}CLK)") (class "Default")
      (node (ref "IC5") (pin "4") (pinfunction "RT/CLK_4") (pintype "bidirectional"))
      (node (ref "R27") (pin "2") (pinfunction "2_2") (pintype "passive"))
    )
    (net (code "58") (name "Net-(IC5-SW)") (class "Default")
      (node (ref "C37") (pin "2") (pinfunction "2_2") (pintype "passive"))
      (node (ref "D5") (pin "C") (pinfunction "C_C") (pintype "passive"))
      (node (ref "IC5") (pin "8") (pinfunction "SW_8") (pintype "bidirectional"))
      (node (ref "L5") (pin "1") (pinfunction "1_1") (pintype "bidirectional"))
    )
    (net (code "59") (name "Net-(IC7-BOOT)") (class "Default")
      (node (ref "C55") (pin "1") (pinfunction "1_1") (pintype "passive"))
      (node (ref "IC7") (pin "1") (pinfunction "BOOT_1") (pintype "bidirectional"))
    )
    (net (code "60") (name "Net-(IC7-COMP)") (class "Default")
      (node (ref "C60") (pin "2") (pinfunction "2_2") (pintype "passive"))
      (node (ref "IC7") (pin "6") (pinfunction "COMP_6") (pintype "bidirectional"))
      (node (ref "R40") (pin "2") (pinfunction "2_2") (pintype "passive"))
    )
    (net (code "61") (name "Net-(IC7-EN)") (class "Default")
      (node (ref "IC7") (pin "3") (pinfunction "EN_3") (pintype "bidirectional"))
      (node (ref "R5") (pin "2") (pinfunction "2_2") (pintype "passive"))
    )
    (net (code "62") (name "Net-(IC7-FB)") (class "Default")
      (node (ref "IC7") (pin "5") (pinfunction "FB_5") (pintype "bidirectional"))
      (node (ref "R41") (pin "1") (pinfunction "1_1") (pintype "passive"))
      (node (ref "R42") (pin "2") (pinfunction "2_2") (pintype "passive"))
    )
    (net (code "63") (name "Net-(IC7-RT{slash}CLK)") (class "Default")
      (node (ref "IC7") (pin "4") (pinfunction "RT/CLK_4") (pintype "bidirectional"))
      (node (ref "R39") (pin "2") (pinfunction "2_2") (pintype "passive"))
    )
    (net (code "64") (name "Net-(IC7-SW)") (class "Default")
      (node (ref "C55") (pin "2") (pinfunction "2_2") (pintype "passive"))
      (node (ref "D7") (pin "C") (pinfunction "C_C") (pintype "passive"))
      (node (ref "IC7") (pin "8") (pinfunction "SW_8") (pintype "bidirectional"))
      (node (ref "L7") (pin "1") (pinfunction "1_1") (pintype "bidirectional"))
    )
    (net (code "65") (name "Net-(LED1-PadA)") (class "Default")
      (node (ref "LED1") (pin "A") (pinfunction "A_A") (pintype "bidirectional"))
      (node (ref "R7") (pin "2") (pinfunction "2_2") (pintype "passive"))
    )
    (net (code "66") (name "Net-(LED2-PadA)") (class "Default")
      (node (ref "LED2") (pin "A") (pinfunction "A_A") (pintype "bidirectional"))
      (node (ref "R8") (pin "2") (pinfunction "2_2") (pintype "passive"))
    )
    (net (code "67") (name "Net-(LED3-PadA)") (class "Default")
      (node (ref "LED3") (pin "A") (pinfunction "A_A") (pintype "bidirectional"))
      (node (ref "R16") (pin "2") (pinfunction "2_2") (pintype "passive"))
    )
    (net (code "68") (name "Net-(LED4-PadA)") (class "Default")
      (node (ref "LED4") (pin "A") (pinfunction "A_A") (pintype "bidirectional"))
      (node (ref "R18") (pin "2") (pinfunction "2_2") (pintype "passive"))
    )
    (net (code "69") (name "Net-(Q1-G)") (class "Default")
      (node (ref "Q1") (pin "1") (pinfunction "G_1") (pintype "passive"))
      (node (ref "R20") (pin "1") (pinfunction "1_1") (pintype "passive"))
    )
    (net (code "70") (name "Net-(Q2_-G)") (class "Default")
      (node (ref "CON24") (pin "1") (pinfunction "1_1") (pintype "bidirectional"))
      (node (ref "CON24") (pin "2") (pinfunction "2_2") (pintype "bidirectional"))
      (node (ref "Q2") (pin "G") (pinfunction "G_G") (pintype "passive"))
      (node (ref "Q2_") (pin "4G") (pinfunction "G_4G") (pintype "passive"))
      (node (ref "Q3") (pin "G") (pinfunction "G_G") (pintype "passive"))
      (node (ref "Q3_") (pin "4G") (pinfunction "G_4G") (pintype "passive"))
      (node (ref "Q4") (pin "G") (pinfunction "G_G") (pintype "passive"))
      (node (ref "Q4_") (pin "4G") (pinfunction "G_4G") (pintype "passive"))
      (node (ref "R21") (pin "2") (pinfunction "2_2") (pintype "passive"))
      (node (ref "ZD1") (pin "C") (pinfunction "C_C") (pintype "passive"))
    )
    (net (code "71") (name "Net-(R2-Pad2)") (class "Default")
      (node (ref "R2") (pin "2") (pinfunction "2_2") (pintype "passive"))
      (node (ref "SJ2") (pin "1") (pinfunction "1_1") (pintype "passive"))
    )
    (net (code "72") (name "Net-(R14-Pad1)") (class "Default")
      (node (ref "R14") (pin "1") (pinfunction "1_1") (pintype "passive"))
      (node (ref "R15") (pin "2") (pinfunction "2_2") (pintype "passive"))
    )
    (net (code "73") (name "Net-(R21-Pad1)") (class "Default")
      (node (ref "R21") (pin "1") (pinfunction "1_1") (pintype "passive"))
      (node (ref "R24") (pin "2") (pinfunction "2_2") (pintype "passive"))
    )
    (net (code "74") (name "OTG_DM1") (class "Default")
      (node (ref "CON1") (pin "33") (pinfunction "OTG_DM1_33") (pintype "bidirectional"))
      (node (ref "CON14") (pin "4") (pinfunction "4_4") (pintype "passive"))
      (node (ref "CON19") (pin "A7") (pinfunction "D-_A7") (pintype "bidirectional"))
      (node (ref "CON19") (pin "B7") (pinfunction "D-_B7") (pintype "bidirectional"))
    )
    (net (code "75") (name "OTG_DP1") (class "Default")
      (node (ref "CON1") (pin "31") (pinfunction "OTG_DP1_31") (pintype "bidirectional"))
      (node (ref "CON14") (pin "3") (pinfunction "3_3") (pintype "passive"))
      (node (ref "CON19") (pin "A6") (pinfunction "D+_A6") (pintype "bidirectional"))
      (node (ref "CON19") (pin "B6") (pinfunction "D+_B6") (pintype "bidirectional"))
    )
    (net (code "76") (name "PGND") (class "Default")
      (node (ref "J1") (pin "2") (pinfunction "P$2_2") (pintype "bidirectional"))
      (node (ref "M1") (pin "2") (pinfunction "P$1_2") (pintype "bidirectional"))
      (node (ref "M2") (pin "2") (pinfunction "P$1_2") (pintype "bidirectional"))
      (node (ref "M3") (pin "2") (pinfunction "P$1_2") (pintype "bidirectional"))
      (node (ref "M4") (pin "2") (pinfunction "P$1_2") (pintype "bidirectional"))
      (node (ref "M5") (pin "2") (pinfunction "P$1_2") (pintype "bidirectional"))
      (node (ref "M6") (pin "2") (pinfunction "P$1_2") (pintype "bidirectional"))
      (node (ref "Q2") (pin "S") (pinfunction "S_S") (pintype "passive"))
      (node (ref "Q2_") (pin "1S") (pinfunction "S_1S") (pintype "passive"))
      (node (ref "Q2_") (pin "2S") (pinfunction "S_2S") (pintype "passive"))
      (node (ref "Q2_") (pin "3S") (pinfunction "S_3S") (pintype "passive"))
      (node (ref "Q3") (pin "S") (pinfunction "S_S") (pintype "passive"))
      (node (ref "Q3_") (pin "1S") (pinfunction "S_1S") (pintype "passive"))
      (node (ref "Q3_") (pin "2S") (pinfunction "S_2S") (pintype "passive"))
      (node (ref "Q3_") (pin "3S") (pinfunction "S_3S") (pintype "passive"))
      (node (ref "Q4") (pin "S") (pinfunction "S_S") (pintype "passive"))
      (node (ref "Q4_") (pin "1S") (pinfunction "S_1S") (pintype "passive"))
      (node (ref "Q4_") (pin "2S") (pinfunction "S_2S") (pintype "passive"))
      (node (ref "Q4_") (pin "3S") (pinfunction "S_3S") (pintype "passive"))
    )
    (net (code "77") (name "PPM-SBUS-PROT") (class "Default")
      (node (ref "CON1") (pin "62") (pinfunction "PPM-SBUS-PROT_62") (pintype "bidirectional"))
      (node (ref "CON2") (pin "3") (pinfunction "3_3") (pintype "bidirectional"))
    )
    (net (code "78") (name "SERIAL1_RX") (class "Default")
      (node (ref "CON1") (pin "38") (pinfunction "SERIAL1_RX_38") (pintype "bidirectional"))
      (node (ref "CON4") (pin "4") (pinfunction "4_4") (pintype "bidirectional"))
    )
    (net (code "79") (name "SERIAL1_TX") (class "Default")
      (node (ref "CON1") (pin "40") (pinfunction "SERIAL1_TX_40") (pintype "bidirectional"))
      (node (ref "CON4") (pin "3") (pinfunction "3_3") (pintype "bidirectional"))
    )
    (net (code "80") (name "SERIAL2_RX") (class "Default")
      (node (ref "CON1") (pin "34") (pinfunction "SERIAL2_RX_34") (pintype "bidirectional"))
      (node (ref "CON18") (pin "8") (pinfunction "8_8") (pintype "passive"))
    )
    (net (code "81") (name "SERIAL2_TX") (class "Default")
      (node (ref "CON1") (pin "36") (pinfunction "SERIAL2_TX_36") (pintype "bidirectional"))
      (node (ref "CON18") (pin "7") (pinfunction "7_7") (pintype "passive"))
    )
    (net (code "82") (name "SERIAL4_RX") (class "Default")
      (node (ref "CON1") (pin "16") (pinfunction "SERIAL4_RX_16") (pintype "bidirectional"))
      (node (ref "CON17") (pin "4") (pinfunction "4_4") (pintype "bidirectional"))
    )
    (net (code "83") (name "SERIAL4_TX") (class "Default")
      (node (ref "CON1") (pin "18") (pinfunction "SERIAL4_TX_18") (pintype "bidirectional"))
      (node (ref "CON17") (pin "3") (pinfunction "3_3") (pintype "bidirectional"))
    )
    (net (code "84") (name "SERIAL5_RX") (class "Default")
      (node (ref "CON1") (pin "12") (pinfunction "SERIAL5_RX_12") (pintype "bidirectional"))
      (node (ref "CON13") (pin "4") (pinfunction "4_4") (pintype "bidirectional"))
    )
    (net (code "85") (name "SERIAL5_TX") (class "Default")
      (node (ref "CON1") (pin "14") (pinfunction "SERIAL5_TX_14") (pintype "bidirectional"))
      (node (ref "CON13") (pin "3") (pinfunction "3_3") (pintype "bidirectional"))
    )
    (net (code "86") (name "VBAT") (class "Default")
      (node (ref "BAT1PAD1") (pin "1") (pinfunction "P$1_1") (pintype "bidirectional"))
      (node (ref "BAT2PAD1") (pin "1") (pinfunction "P$1_1") (pintype "bidirectional"))
      (node (ref "BAT3PAD1") (pin "1") (pinfunction "P$1_1") (pintype "bidirectional"))
      (node (ref "R14") (pin "2") (pinfunction "2_2") (pintype "passive"))
      (node (ref "R4") (pin "1") (pinfunction "1_1") (pintype "bidirectional"))
      (node (ref "R4") (pin "11") (pinfunction "1_11") (pintype "bidirectional"))
    )
    (net (code "87") (name "VBUS") (class "Default")
      (node (ref "CON1") (pin "29") (pinfunction "VBUS_29") (pintype "bidirectional"))
      (node (ref "CON14") (pin "2") (pinfunction "2_2") (pintype "passive"))
      (node (ref "CON19") (pin "A4") (pinfunction "VBUS_A4") (pintype "bidirectional"))
      (node (ref "CON19") (pin "B4") (pinfunction "VBUS_B4") (pintype "bidirectional"))
      (node (ref "D1") (pin "A") (pinfunction "A_A") (pintype "passive"))
    )
    (net (code "88") (name "VDC") (class "Default")
      (node (ref "C11") (pin "2") (pinfunction "2_2") (pintype "passive"))
      (node (ref "C12") (pin "2") (pinfunction "2_2") (pintype "passive"))
      (node (ref "C13") (pin "2") (pinfunction "2_2") (pintype "passive"))
      (node (ref "C38") (pin "2") (pinfunction "2_2") (pintype "passive"))
      (node (ref "C39") (pin "2") (pinfunction "2_2") (pintype "passive"))
      (node (ref "C40") (pin "2") (pinfunction "2_2") (pintype "passive"))
      (node (ref "C56") (pin "2") (pinfunction "2_2") (pintype "passive"))
      (node (ref "C57") (pin "2") (pinfunction "2_2") (pintype "passive"))
      (node (ref "C58") (pin "2") (pinfunction "2_2") (pintype "passive"))
      (node (ref "IC2") (pin "2") (pinfunction "VIN_2") (pintype "bidirectional"))
      (node (ref "IC5") (pin "2") (pinfunction "VIN_2") (pintype "bidirectional"))
      (node (ref "IC7") (pin "2") (pinfunction "VIN_2") (pintype "bidirectional"))
      (node (ref "M1") (pin "1") (pinfunction "P$1_1") (pintype "bidirectional"))
      (node (ref "M2") (pin "1") (pinfunction "P$1_1") (pintype "bidirectional"))
      (node (ref "M3") (pin "1") (pinfunction "P$1_1") (pintype "bidirectional"))
      (node (ref "M4") (pin "1") (pinfunction "P$1_1") (pintype "bidirectional"))
      (node (ref "M5") (pin "1") (pinfunction "P$1_1") (pintype "bidirectional"))
      (node (ref "M6") (pin "1") (pinfunction "P$1_1") (pintype "bidirectional"))
      (node (ref "R24") (pin "1") (pinfunction "1_1") (pintype "passive"))
      (node (ref "R4") (pin "2") (pinfunction "2_2") (pintype "bidirectional"))
      (node (ref "R4") (pin "22") (pinfunction "2_22") (pintype "bidirectional"))
    )
    (net (code "89") (name "VDD_5V") (class "Default")
      (node (ref "C1") (pin "2") (pinfunction "2_2") (pintype "passive"))
      (node (ref "CON1") (pin "61") (pinfunction "VDD_5V_61") (pintype "bidirectional"))
      (node (ref "CON1") (pin "63") (pinfunction "VDD_5V_63") (pintype "bidirectional"))
      (node (ref "CON10") (pin "1") (pinfunction "1_1") (pintype "bidirectional"))
      (node (ref "CON11") (pin "1") (pinfunction "1_1") (pintype "bidirectional"))
      (node (ref "CON12") (pin "1") (pinfunction "1_1") (pintype "bidirectional"))
      (node (ref "CON13") (pin "2") (pinfunction "2_2") (pintype "bidirectional"))
      (node (ref "CON15") (pin "2") (pinfunction "2_2") (pintype "passive"))
      (node (ref "CON17") (pin "2") (pinfunction "2_2") (pintype "bidirectional"))
      (node (ref "CON2") (pin "2") (pinfunction "2_2") (pintype "bidirectional"))
      (node (ref "CON20") (pin "1") (pinfunction "1_1") (pintype "bidirectional"))
      (node (ref "CON21") (pin "1") (pinfunction "1_1") (pintype "bidirectional"))
      (node (ref "CON22") (pin "7") (pinfunction "7_7") (pintype "passive"))
      (node (ref "CON22") (pin "8") (pinfunction "8_8") (pintype "passive"))
      (node (ref "CON4") (pin "2") (pinfunction "2_2") (pintype "bidirectional"))
      (node (ref "CON6") (pin "1") (pinfunction "1_1") (pintype "bidirectional"))
      (node (ref "CON7") (pin "1") (pinfunction "1_1") (pintype "bidirectional"))
      (node (ref "CON8") (pin "1") (pinfunction "1_1") (pintype "bidirectional"))
      (node (ref "CON9") (pin "1") (pinfunction "1_1") (pintype "bidirectional"))
      (node (ref "D1") (pin "C") (pinfunction "C_C") (pintype "passive"))
      (node (ref "IC1") (pin "5") (pinfunction "V+_5") (pintype "bidirectional"))
      (node (ref "R16") (pin "1") (pinfunction "1_1") (pintype "passive"))
      (node (ref "R18") (pin "1") (pinfunction "1_1") (pintype "passive"))
      (node (ref "R23") (pin "P$2") (pinfunction "2_P$2") (pintype "passive"))
      (node (ref "SJ1") (pin "2") (pinfunction "2_2") (pintype "passive"))
    )
    (net (code "90") (name "VDD_12V") (class "Default")
      (node (ref "C61") (pin "2") (pinfunction "2_2") (pintype "passive"))
      (node (ref "C62") (pin "2") (pinfunction "2_2") (pintype "passive"))
      (node (ref "C63") (pin "2") (pinfunction "2_2") (pintype "passive"))
      (node (ref "CON22") (pin "10") (pinfunction "10_10") (pintype "passive"))
      (node (ref "CON22") (pin "11") (pinfunction "11_11") (pintype "passive"))
      (node (ref "CON22") (pin "9") (pinfunction "9_9") (pintype "passive"))
      (node (ref "CON3") (pin "2") (pinfunction "2_2") (pintype "bidirectional"))
      (node (ref "CON3") (pin "3") (pinfunction "3_3") (pintype "bidirectional"))
      (node (ref "L7") (pin "2") (pinfunction "2_2") (pintype "bidirectional"))
      (node (ref "PAD15") (pin "P$1") (pinfunction "P$1_P$1") (pintype "bidirectional"))
      (node (ref "R22") (pin "P$2") (pinfunction "2_P$2") (pintype "passive"))
      (node (ref "R41") (pin "2") (pinfunction "2_2") (pintype "passive"))
      (node (ref "R7") (pin "1") (pinfunction "1_1") (pintype "passive"))
    )
    (net (code "91") (name "VDD_24V") (class "Default")
      (node (ref "C16") (pin "P$2") (pinfunction "2_P$2") (pintype "passive"))
      (node (ref "C17") (pin "P$2") (pinfunction "2_P$2") (pintype "passive"))
      (node (ref "C18") (pin "P$2") (pinfunction "2_P$2") (pintype "passive"))
      (node (ref "CON18") (pin "10") (pinfunction "10_10") (pintype "passive"))
      (node (ref "CON18") (pin "11") (pinfunction "11_11") (pintype "passive"))
      (node (ref "CON18") (pin "9") (pinfunction "9_9") (pintype "passive"))
      (node (ref "L4") (pin "2") (pinfunction "2_2") (pintype "bidirectional"))
      (node (ref "PAD17") (pin "P$1") (pinfunction "P$1_P$1") (pintype "bidirectional"))
      (node (ref "R11") (pin "2") (pinfunction "2_2") (pintype "passive"))
      (node (ref "R8") (pin "1") (pinfunction "1_1") (pintype "passive"))
    )
    (net (code "92") (name "unconnected-(CON1-3.3V_SPEKTRUM_EN-Pad19)") (class "Default")
      (node (ref "CON1") (pin "19") (pinfunction "3.3V_SPEKTRUM_EN_19") (pintype "bidirectional"))
    )
    (net (code "93") (name "unconnected-(CON1-AUX_BATT_CURRENT_SENS-Pad25)") (class "Default")
      (node (ref "CON1") (pin "25") (pinfunction "AUX_BATT_CURRENT_SENS_25") (pintype "bidirectional"))
    )
    (net (code "94") (name "unconnected-(CON1-AUX_BATT_VOLTAGE_SENS-Pad23)") (class "Default")
      (node (ref "CON1") (pin "23") (pinfunction "AUX_BATT_VOLTAGE_SENS_23") (pintype "bidirectional"))
    )
    (net (code "95") (name "unconnected-(CON1-CAN3_H-Pad10)") (class "Default")
      (node (ref "CON1") (pin "10") (pinfunction "CAN3_H_10") (pintype "bidirectional"))
    )
    (net (code "96") (name "unconnected-(CON1-CAN3_L-Pad8)") (class "Default")
      (node (ref "CON1") (pin "8") (pinfunction "CAN3_L_8") (pintype "bidirectional"))
    )
    (net (code "97") (name "unconnected-(CON1-EXTERN_DRDY-Pad11)") (class "Default")
      (node (ref "CON1") (pin "11") (pinfunction "EXTERN_DRDY_11") (pintype "bidirectional"))
    )
    (net (code "98") (name "unconnected-(CON1-FMU-SWCLK-Pad3)") (class "Default")
      (node (ref "CON1") (pin "3") (pinfunction "FMU-SWCLK_3") (pintype "bidirectional"))
    )
    (net (code "99") (name "unconnected-(CON1-FMU-SWDIO-Pad1)") (class "Default")
      (node (ref "CON1") (pin "1") (pinfunction "FMU-SWDIO_1") (pintype "bidirectional"))
    )
    (net (code "100") (name "unconnected-(CON1-FMU-~{RESET}-Pad7)") (class "Default")
      (node (ref "CON1") (pin "7") (pinfunction "FMU-~{RESET}_7") (pintype "bidirectional"))
    )
    (net (code "101") (name "unconnected-(CON1-I2C1_SCL-Pad37)") (class "Default")
      (node (ref "CON1") (pin "37") (pinfunction "I2C1_SCL_37") (pintype "bidirectional"))
    )
    (net (code "102") (name "unconnected-(CON1-I2C1_SDA-Pad35)") (class "Default")
      (node (ref "CON1") (pin "35") (pinfunction "I2C1_SDA_35") (pintype "bidirectional"))
    )
    (net (code "103") (name "unconnected-(CON1-IO-CH6-PROT-Pad70)") (class "Default")
      (node (ref "CON1") (pin "70") (pinfunction "IO-CH6-PROT_70") (pintype "bidirectional"))
    )
    (net (code "104") (name "unconnected-(CON1-IO-SWCLK-Pad71)") (class "Default")
      (node (ref "CON1") (pin "71") (pinfunction "IO-SWCLK_71") (pintype "bidirectional"))
    )
    (net (code "105") (name "unconnected-(CON1-IO-SWDIO-Pad69)") (class "Default")
      (node (ref "CON1") (pin "69") (pinfunction "IO-SWDIO_69") (pintype "bidirectional"))
    )
    (net (code "106") (name "unconnected-(CON1-IO-~{RESET}-Pad75)") (class "Default")
      (node (ref "CON1") (pin "75") (pinfunction "IO-~{RESET}_75") (pintype "bidirectional"))
    )
    (net (code "107") (name "unconnected-(CON1-IO_USART1_RX-Pad48)") (class "Default")
      (node (ref "CON1") (pin "48") (pinfunction "IO_USART1_RX_48") (pintype "bidirectional"))
    )
    (net (code "108") (name "unconnected-(CON1-IO_USART1_TX-Pad46)") (class "Default")
      (node (ref "CON1") (pin "46") (pinfunction "IO_USART1_TX_46") (pintype "bidirectional"))
    )
    (net (code "109") (name "unconnected-(CON1-IO_VDD_3V3-Pad26)") (class "Default")
      (node (ref "CON1") (pin "26") (pinfunction "IO_VDD_3V3_26") (pintype "bidirectional"))
    )
    (net (code "110") (name "unconnected-(CON1-IO_VDD_5V5-Pad65)") (class "Default")
      (node (ref "CON1") (pin "65") (pinfunction "IO_VDD_5V5_65") (pintype "bidirectional"))
    )
    (net (code "111") (name "unconnected-(CON1-PRESSURE_SENS_IN-Pad21)") (class "Default")
      (node (ref "CON1") (pin "21") (pinfunction "PRESSURE_SENS_IN_21") (pintype "bidirectional"))
    )
    (net (code "112") (name "unconnected-(CON1-S.BUS_OUT-Pad64)") (class "Default")
      (node (ref "CON1") (pin "64") (pinfunction "S.BUS_OUT_64") (pintype "bidirectional"))
    )
    (net (code "113") (name "unconnected-(CON1-SAFETY-Pad17)") (class "Default")
      (node (ref "CON1") (pin "17") (pinfunction "SAFETY_17") (pintype "bidirectional"))
    )
    (net (code "114") (name "unconnected-(CON1-SERIAL1_CTS-Pad44)") (class "Default")
      (node (ref "CON1") (pin "44") (pinfunction "SERIAL1_CTS_44") (pintype "bidirectional"))
    )
    (net (code "115") (name "unconnected-(CON1-SERIAL1_RTS-Pad42)") (class "Default")
      (node (ref "CON1") (pin "42") (pinfunction "SERIAL1_RTS_42") (pintype "bidirectional"))
    )
    (net (code "116") (name "unconnected-(CON1-SERIAL2_CTS-Pad32)") (class "Default")
      (node (ref "CON1") (pin "32") (pinfunction "SERIAL2_CTS_32") (pintype "bidirectional"))
    )
    (net (code "117") (name "unconnected-(CON1-SERIAL2_RTS-Pad30)") (class "Default")
      (node (ref "CON1") (pin "30") (pinfunction "SERIAL2_RTS_30") (pintype "bidirectional"))
    )
    (net (code "118") (name "unconnected-(CON1-SERIAL3_RX-Pad20)") (class "Default")
      (node (ref "CON1") (pin "20") (pinfunction "SERIAL3_RX_20") (pintype "bidirectional"))
    )
    (net (code "119") (name "unconnected-(CON1-SERIAL3_TX-Pad22)") (class "Default")
      (node (ref "CON1") (pin "22") (pinfunction "SERIAL3_TX_22") (pintype "bidirectional"))
    )
    (net (code "120") (name "unconnected-(CON1-SPI_EXT_MISO-Pad67)") (class "Default")
      (node (ref "CON1") (pin "67") (pinfunction "SPI_EXT_MISO_67") (pintype "bidirectional"))
    )
    (net (code "121") (name "unconnected-(CON1-SPI_EXT_MOSI-Pad51)") (class "Default")
      (node (ref "CON1") (pin "51") (pinfunction "SPI_EXT_MOSI_51") (pintype "bidirectional"))
    )
    (net (code "122") (name "unconnected-(CON1-SPI_EXT_SCK-Pad73)") (class "Default")
      (node (ref "CON1") (pin "73") (pinfunction "SPI_EXT_SCK_73") (pintype "bidirectional"))
    )
    (net (code "123") (name "unconnected-(CON1-VDD_SERVO-Pad53)") (class "Default")
      (node (ref "CON1") (pin "53") (pinfunction "VDD_SERVO_53") (pintype "bidirectional"))
    )
    (net (code "124") (name "unconnected-(CON1-VDD_SERVO_IN-Pad9)") (class "Default")
      (node (ref "CON1") (pin "9") (pinfunction "VDD_SERVO_IN_9") (pintype "bidirectional"))
    )
    (net (code "125") (name "unconnected-(CON1-~{EXTERN_CS}-Pad5)") (class "Default")
      (node (ref "CON1") (pin "5") (pinfunction "~{EXTERN_CS}_5") (pintype "bidirectional"))
    )
    (net (code "126") (name "unconnected-(CON1-~{IO-LED_SAFET_PROT}-Pad28)") (class "Default")
      (node (ref "CON1") (pin "28") (pinfunction "~{IO-LED_SAFET_PROT}_28") (pintype "bidirectional"))
    )
    (net (code "127") (name "unconnected-(CON1-~{VBUS_VALID}-Pad59)") (class "Default")
      (node (ref "CON1") (pin "59") (pinfunction "~{VBUS_VALID}_59") (pintype "bidirectional"))
    )
    (net (code "128") (name "unconnected-(CON1-~{VDD_5V_HIPOWER_OC}-Pad45)") (class "Default")
      (node (ref "CON1") (pin "45") (pinfunction "~{VDD_5V_HIPOWER_OC}_45") (pintype "bidirectional"))
    )
    (net (code "129") (name "unconnected-(CON1-~{VDD_5V_PERIPH_EN}-Pad27)") (class "Default")
      (node (ref "CON1") (pin "27") (pinfunction "~{VDD_5V_PERIPH_EN}_27") (pintype "bidirectional"))
    )
    (net (code "130") (name "unconnected-(CON1-~{VDD_5V_PERIPH_OC}-Pad43)") (class "Default")
      (node (ref "CON1") (pin "43") (pinfunction "~{VDD_5V_PERIPH_OC}_43") (pintype "bidirectional"))
    )
    (net (code "131") (name "unconnected-(CON1-~{VDD_BACKUP_VALID}-Pad57)") (class "Default")
      (node (ref "CON1") (pin "57") (pinfunction "~{VDD_BACKUP_VALID}_57") (pintype "bidirectional"))
    )
    (net (code "132") (name "unconnected-(IC5-EN-Pad3)") (class "Default")
      (node (ref "IC5") (pin "3") (pinfunction "EN_3") (pintype "bidirectional"))
    )
  )
)
